# electron_v1_3_0.net
KiCad netlist of a schematic drawn in EAGLE
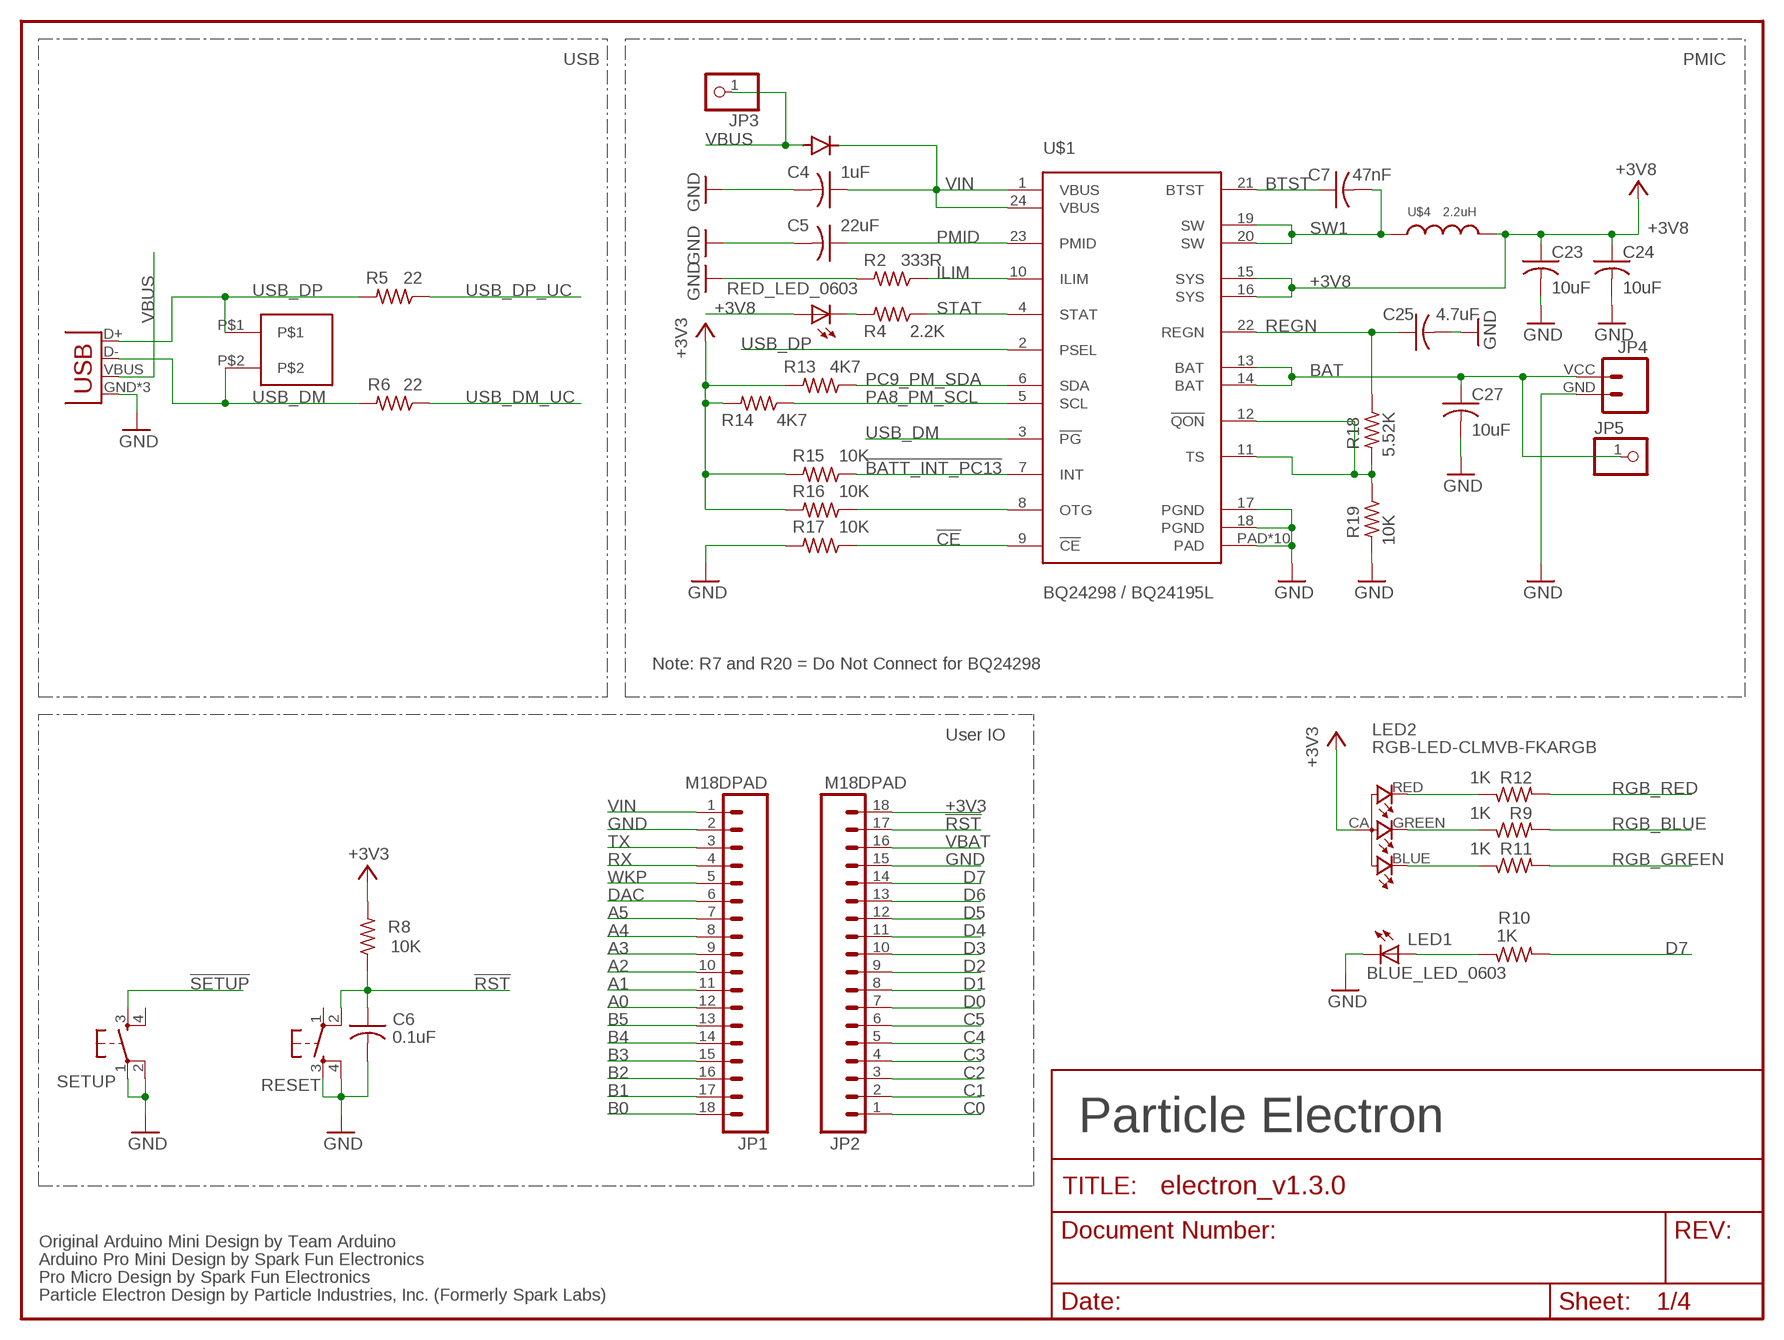
[diagram p0: schematic, sheet 1]
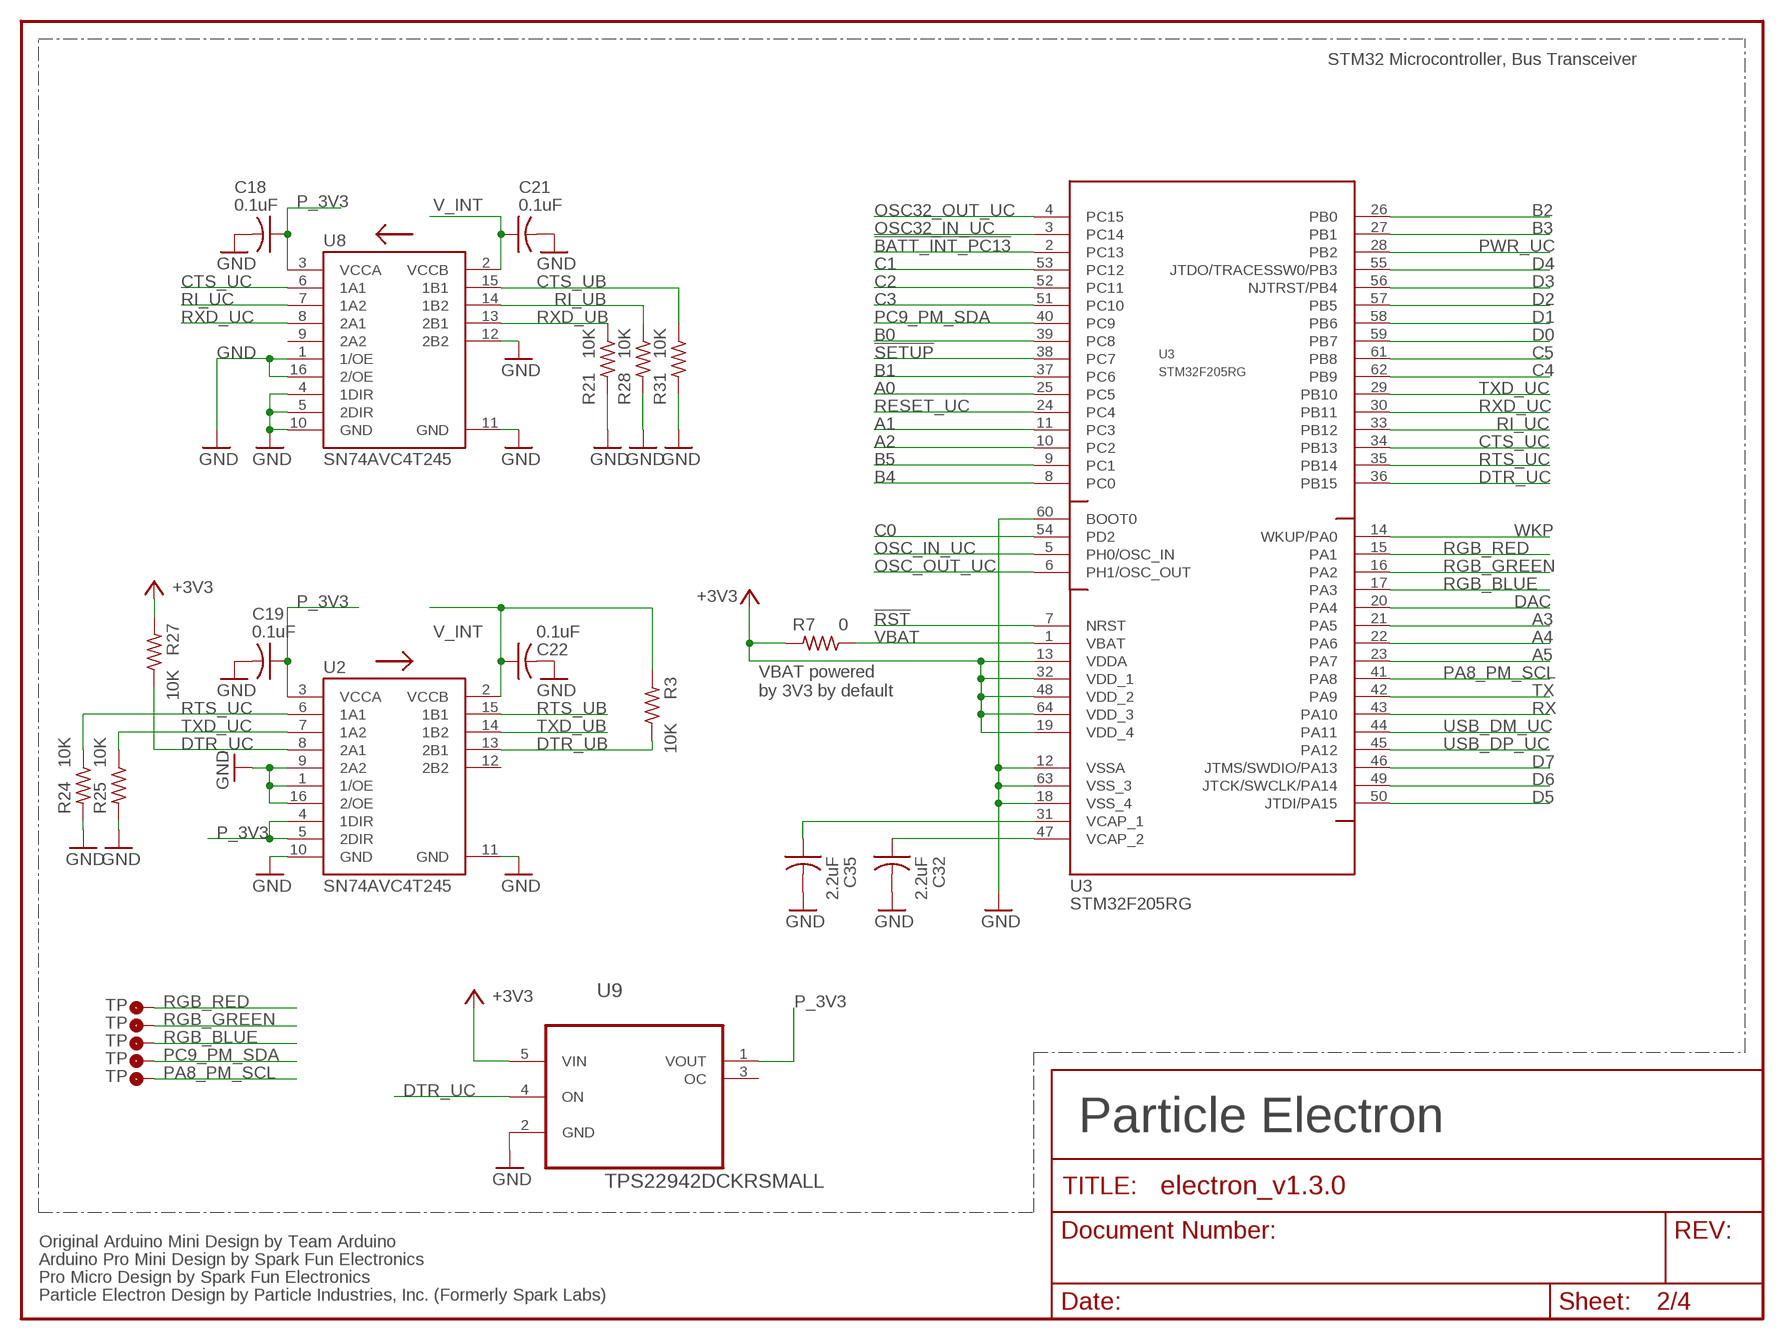
[diagram p1: schematic, sheet 2]
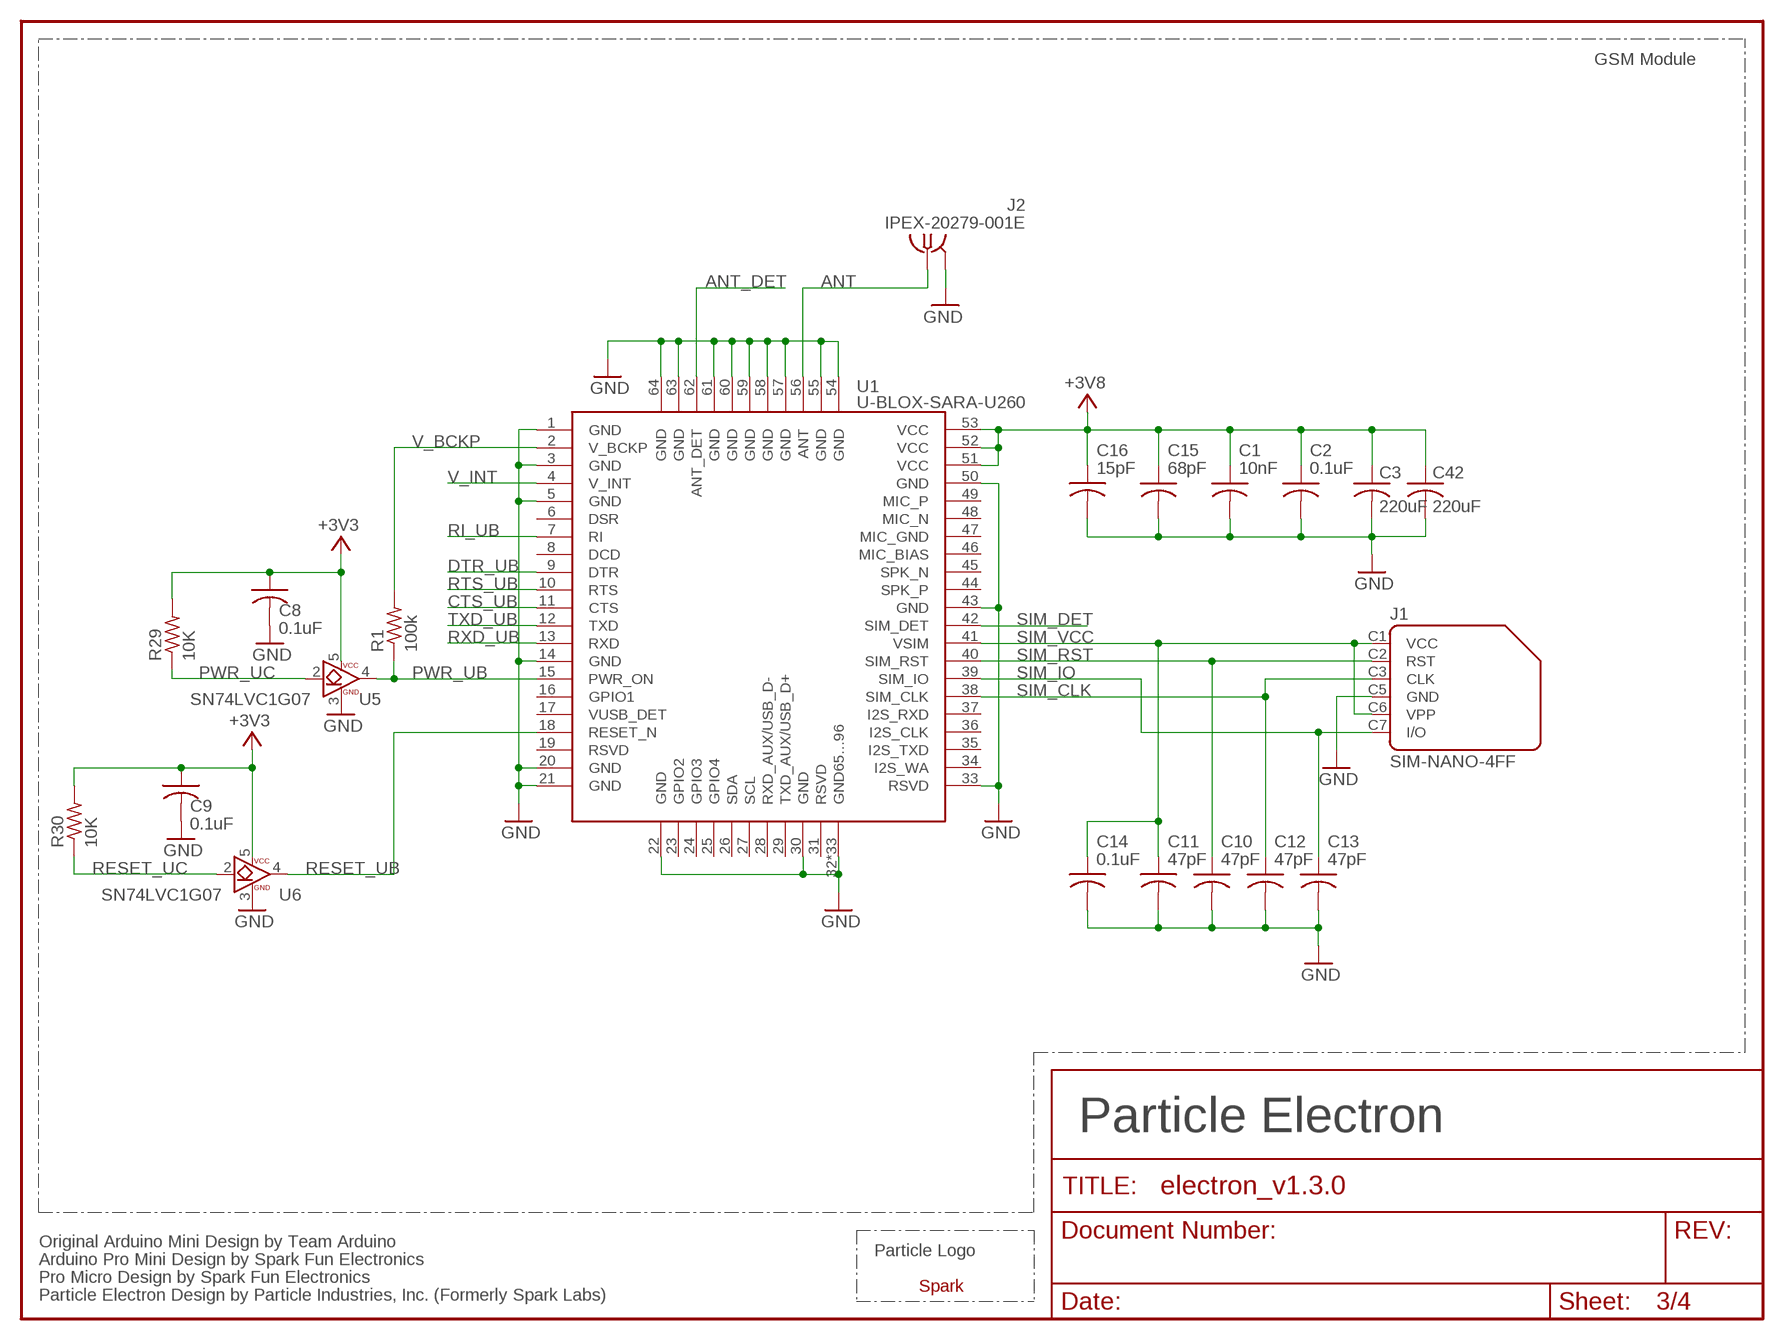
[diagram p2: schematic, sheet 3]
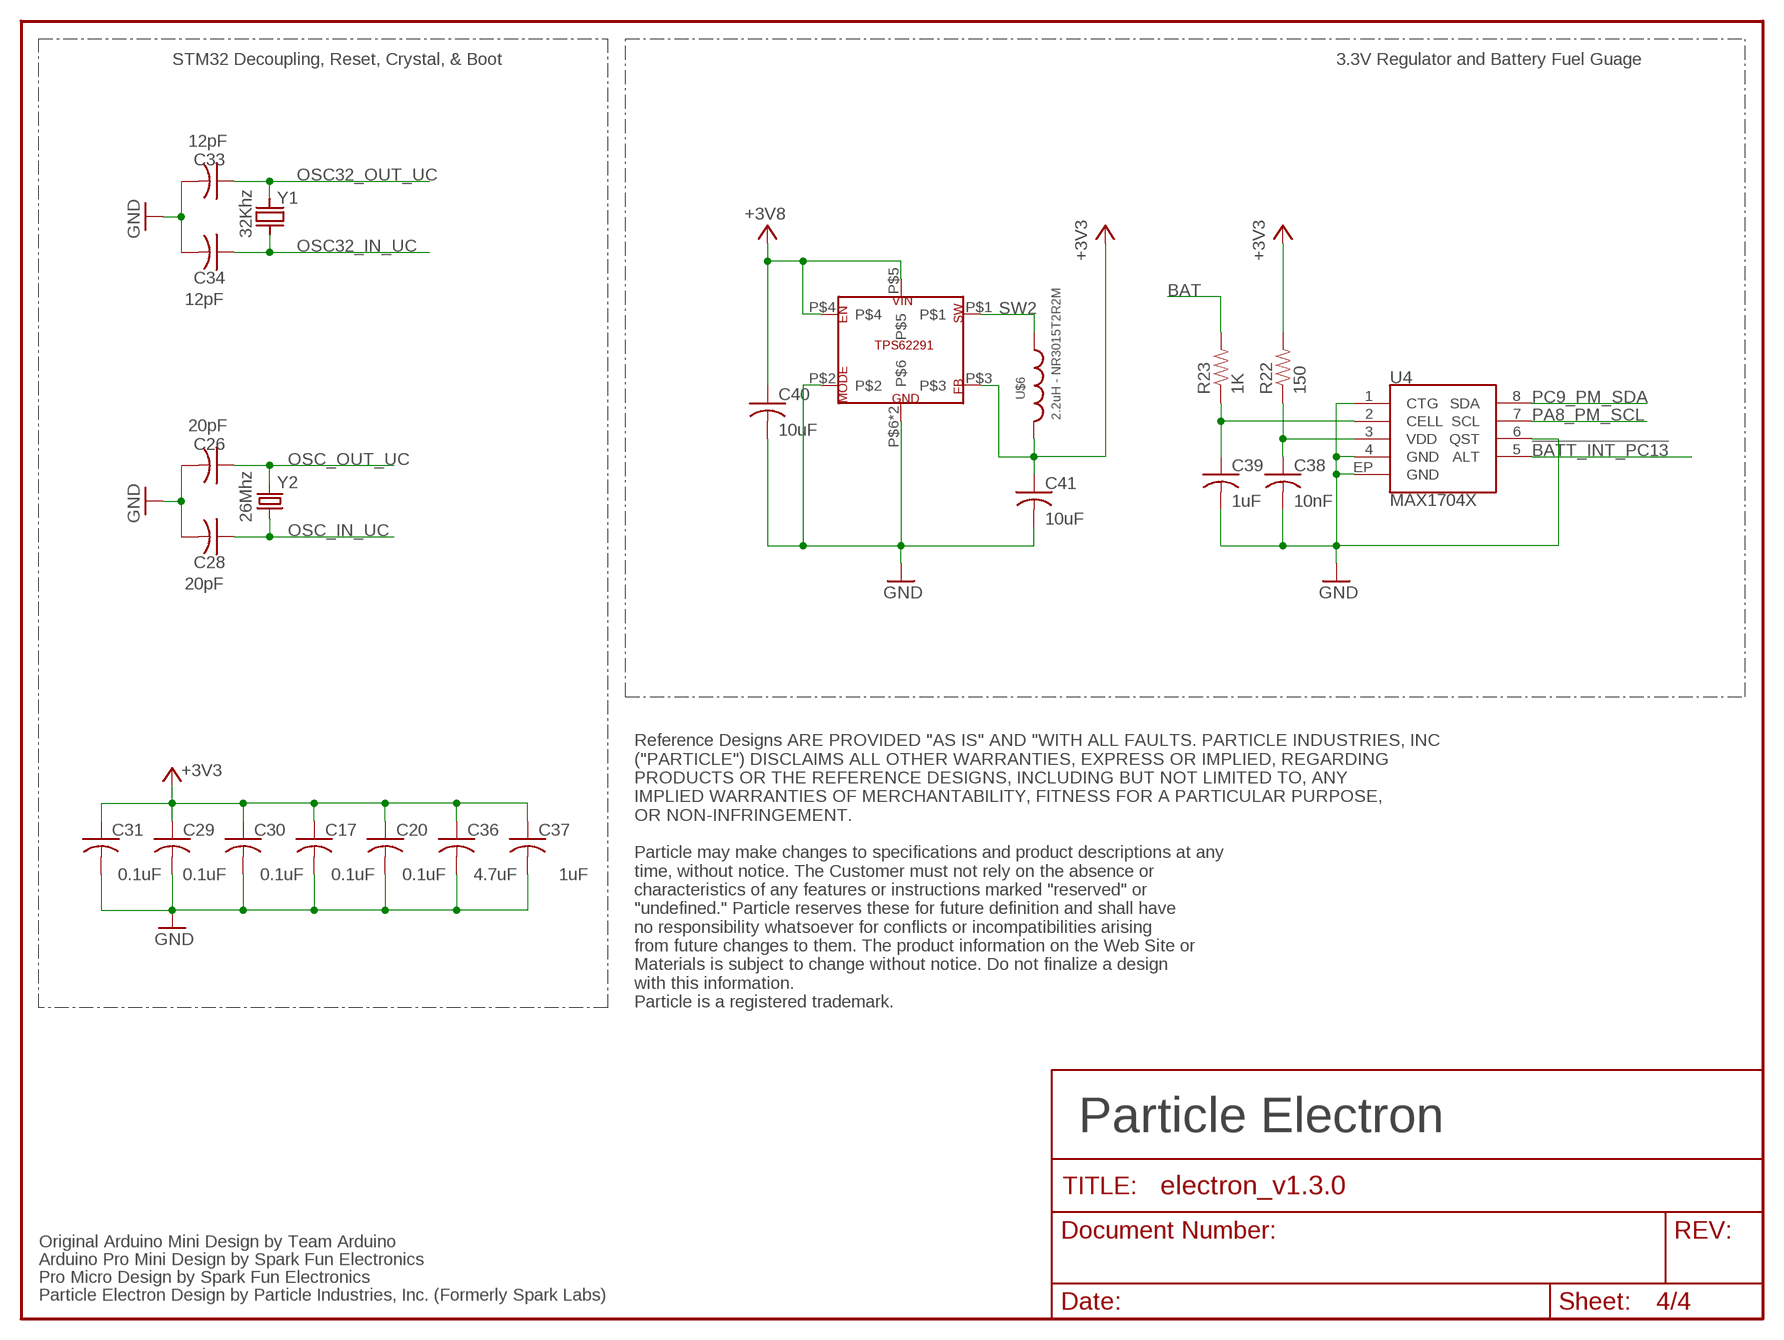
[diagram p3: schematic, sheet 4]

(export (version "E")
  (design (tool "Eeschema 10.0.6"))
  (components
    (comp (ref "C17")
      (value "0.1uF")
      (footprint "eagle-import:C0402_B")
      (libsource (lib "eagle-import") (part "C-US"))
    )
    (comp (ref "C20")
      (value "0.1uF")
      (footprint "eagle-import:C0402_B")
      (libsource (lib "eagle-import") (part "C-US"))
    )
    (comp (ref "C26")
      (value "20pF")
      (footprint "eagle-import:C0402_B")
      (libsource (lib "eagle-import") (part "C-US"))
    )
    (comp (ref "C28")
      (value "20pF")
      (footprint "eagle-import:C0402_B")
      (libsource (lib "eagle-import") (part "C-US"))
    )
    (comp (ref "C29")
      (value "0.1uF")
      (footprint "eagle-import:C0402_B")
      (libsource (lib "eagle-import") (part "C-US"))
    )
    (comp (ref "C30")
      (value "0.1uF")
      (footprint "eagle-import:C0402_B")
      (libsource (lib "eagle-import") (part "C-US"))
    )
    (comp (ref "C31")
      (value "0.1uF")
      (footprint "eagle-import:C0402_B")
      (libsource (lib "eagle-import") (part "C-US"))
    )
    (comp (ref "C33")
      (value "12pF")
      (footprint "eagle-import:C0402_B")
      (libsource (lib "eagle-import") (part "C-US"))
    )
    (comp (ref "C34")
      (value "12pF")
      (footprint "eagle-import:C0402_B")
      (libsource (lib "eagle-import") (part "C-US"))
    )
    (comp (ref "C36")
      (value "4.7uF")
      (footprint "eagle-import:C0402_B")
      (libsource (lib "eagle-import") (part "C-US"))
    )
    (comp (ref "C37")
      (value "1uF")
      (footprint "eagle-import:C0402_B")
      (libsource (lib "eagle-import") (part "C-US"))
    )
    (comp (ref "C38")
      (value "10nF")
      (footprint "eagle-import:C0402_B")
      (libsource (lib "eagle-import") (part "C-US"))
    )
    (comp (ref "C39")
      (value "1uF")
      (footprint "eagle-import:C0402_B")
      (libsource (lib "eagle-import") (part "C-US"))
    )
    (comp (ref "C40")
      (value "10uF")
      (footprint "eagle-import:C0603_B")
      (libsource (lib "eagle-import") (part "C-US0603"))
    )
    (comp (ref "C41")
      (value "10uF")
      (footprint "eagle-import:C0603_B")
      (libsource (lib "eagle-import") (part "C-US0603"))
    )
    (comp (ref "R22")
      (value "150")
      (footprint "eagle-import:0603-RES")
      (libsource (lib "eagle-import") (part "RESISTOR0603-RES"))
    )
    (comp (ref "R23")
      (value "1K")
      (footprint "eagle-import:0603-RES")
      (libsource (lib "eagle-import") (part "RESISTOR0603-RES"))
    )
    (comp (ref "U$5")
      (value "TPS62291DRV")
      (footprint "eagle-import:S-PWSON-N6")
      (libsource (lib "eagle-import") (part "TPS62291DRV"))
    )
    (comp (ref "U$6")
      (value "2.2uH - NR3015T2R2M")
      (footprint "eagle-import:INDUCTOR-NR3015")
      (libsource (lib "eagle-import") (part "INDUCTORB"))
    )
    (comp (ref "U4")
      (value "MAX1704X")
      (footprint "eagle-import:TDFN-8")
      (libsource (lib "eagle-import") (part "MAX1704X"))
    )
    (comp (ref "Y1")
      (value "32Khz")
      (footprint "eagle-import:FC135")
      (libsource (lib "eagle-import") (part "Q_FC135"))
    )
    (comp (ref "Y2")
      (value "26Mhz")
      (footprint "eagle-import:CRYSTAL-SMD-5X3")
      (libsource (lib "eagle-import") (part "CRYSTAL5X3"))
    )
    (comp (ref "C18")
      (value "0.1uF")
      (footprint "eagle-import:C0402_B")
      (libsource (lib "eagle-import") (part "C-US"))
    )
    (comp (ref "C19")
      (value "0.1uF")
      (footprint "eagle-import:C0402_B")
      (libsource (lib "eagle-import") (part "C-US"))
    )
    (comp (ref "C21")
      (value "0.1uF")
      (footprint "eagle-import:C0402_B")
      (libsource (lib "eagle-import") (part "C-US"))
    )
    (comp (ref "C22")
      (value "0.1uF")
      (footprint "eagle-import:C0402_B")
      (libsource (lib "eagle-import") (part "C-US"))
    )
    (comp (ref "C32")
      (value "2.2uF")
      (footprint "eagle-import:C0402_B")
      (libsource (lib "eagle-import") (part "C-US"))
    )
    (comp (ref "C35")
      (value "2.2uF")
      (footprint "eagle-import:C0402_B")
      (libsource (lib "eagle-import") (part "C-US"))
    )
    (comp (ref "R3")
      (value "10K")
      (footprint "eagle-import:R0402_B")
      (libsource (lib "eagle-import") (part "R-US_"))
    )
    (comp (ref "R7")
      (value "0")
      (footprint "eagle-import:R0402_B")
      (libsource (lib "eagle-import") (part "R-US_"))
    )
    (comp (ref "R21")
      (value "10K")
      (footprint "eagle-import:R0402_B")
      (libsource (lib "eagle-import") (part "R-US_"))
    )
    (comp (ref "R24")
      (value "10K")
      (footprint "eagle-import:R0402_B")
      (libsource (lib "eagle-import") (part "R-US_"))
    )
    (comp (ref "R25")
      (value "10K")
      (footprint "eagle-import:R0402_B")
      (libsource (lib "eagle-import") (part "R-US_"))
    )
    (comp (ref "R27")
      (value "10K")
      (footprint "eagle-import:R0402_B")
      (libsource (lib "eagle-import") (part "R-US_"))
    )
    (comp (ref "R28")
      (value "10K")
      (footprint "eagle-import:R0402_B")
      (libsource (lib "eagle-import") (part "R-US_"))
    )
    (comp (ref "R31")
      (value "10K")
      (footprint "eagle-import:R0402_B")
      (libsource (lib "eagle-import") (part "R-US_"))
    )
    (comp (ref "U$8")
      (value "TP0")
      (footprint "eagle-import:TP30_BOT")
      (libsource (lib "eagle-import") (part "TP0"))
    )
    (comp (ref "U$9")
      (value "TP0")
      (footprint "eagle-import:TP30_BOT")
      (libsource (lib "eagle-import") (part "TP0"))
    )
    (comp (ref "U$11")
      (value "TP0")
      (footprint "eagle-import:TP30_BOT")
      (libsource (lib "eagle-import") (part "TP0"))
    )
    (comp (ref "U$12")
      (value "TP0")
      (footprint "eagle-import:TP30_BOT")
      (libsource (lib "eagle-import") (part "TP0"))
    )
    (comp (ref "U$13")
      (value "TP0")
      (footprint "eagle-import:TP30_BOT")
      (libsource (lib "eagle-import") (part "TP0"))
    )
    (comp (ref "U2")
      (value "SN74AVC4T245")
      (footprint "eagle-import:UFQFN-16")
      (libsource (lib "eagle-import") (part "SN74AVC4T245"))
    )
    (comp (ref "U3")
      (value "STM32F205RG")
      (footprint "eagle-import:LQFP64")
      (libsource (lib "eagle-import") (part "STM32F20XR"))
    )
    (comp (ref "U8")
      (value "SN74AVC4T245")
      (footprint "eagle-import:UFQFN-16")
      (libsource (lib "eagle-import") (part "SN74AVC4T245"))
    )
    (comp (ref "U9")
      (value "TPS22942DCKRSMALL")
      (footprint "eagle-import:SC70-5")
      (libsource (lib "eagle-import") (part "TPS22942DCKRSMALL"))
    )
    (comp (ref "BLUE_LED_0603")
      (value "LEDNOSILK")
      (footprint "eagle-import:LED-0603-NS")
      (libsource (lib "eagle-import") (part "LEDNOSILK"))
    )
    (comp (ref "C4")
      (value "1uF")
      (footprint "eagle-import:C0603_B")
      (libsource (lib "eagle-import") (part "C-US0603"))
    )
    (comp (ref "C5")
      (value "22uF")
      (footprint "eagle-import:C0603_B")
      (libsource (lib "eagle-import") (part "C-US0603"))
    )
    (comp (ref "C6")
      (value "0.1uF")
      (footprint "eagle-import:C0402_B")
      (libsource (lib "eagle-import") (part "C-US"))
    )
    (comp (ref "C7")
      (value "47nF")
      (footprint "eagle-import:C0402_B")
      (libsource (lib "eagle-import") (part "C-US"))
    )
    (comp (ref "C23")
      (value "10uF")
      (footprint "eagle-import:C0603_B")
      (libsource (lib "eagle-import") (part "C-US0603"))
    )
    (comp (ref "C24")
      (value "10uF")
      (footprint "eagle-import:C0603_B")
      (libsource (lib "eagle-import") (part "C-US0603"))
    )
    (comp (ref "C25")
      (value "4.7uF")
      (footprint "eagle-import:C0603_B")
      (libsource (lib "eagle-import") (part "C-US0603"))
    )
    (comp (ref "C27")
      (value "10uF")
      (footprint "eagle-import:C0603_B")
      (libsource (lib "eagle-import") (part "C-US0603"))
    )
    (comp (ref "JP1")
      (value "M18DPAD")
      (footprint "eagle-import:1X18-D-PADS")
      (libsource (lib "eagle-import") (part "M18DPAD"))
    )
    (comp (ref "JP2")
      (value "M18DPAD")
      (footprint "eagle-import:1X18-D-PADS")
      (libsource (lib "eagle-import") (part "M18DPAD"))
    )
    (comp (ref "JP3")
      (value "PINHD-1X1NOSILK")
      (footprint "eagle-import:1X01_NO_SILK")
      (libsource (lib "eagle-import") (part "PINHD-1X1NOSILK"))
    )
    (comp (ref "JP4")
      (value "M024UCON-15767")
      (footprint "eagle-import:JST-2-SMD-VERT")
      (libsource (lib "eagle-import") (part "M024UCON-15767"))
    )
    (comp (ref "JP5")
      (value "PINHD-1X1NOSILK")
      (footprint "eagle-import:1X01_NO_SILK")
      (libsource (lib "eagle-import") (part "PINHD-1X1NOSILK"))
    )
    (comp (ref "LED2")
      (value "RGB-LED-CLMVB-FKARGB")
      (footprint "eagle-import:PLCC4-2MM-RGB")
      (libsource (lib "eagle-import") (part "RGB-LED-CLMVB-FKARGB"))
    )
    (comp (ref "R2")
      (value "333R")
      (footprint "eagle-import:R0402_B")
      (libsource (lib "eagle-import") (part "R-US_"))
    )
    (comp (ref "R4")
      (value "2.2K")
      (footprint "eagle-import:R0402_B")
      (libsource (lib "eagle-import") (part "R-US_"))
    )
    (comp (ref "R5")
      (value "22")
      (footprint "eagle-import:R0402_B")
      (libsource (lib "eagle-import") (part "R-US_"))
    )
    (comp (ref "R6")
      (value "22")
      (footprint "eagle-import:R0402_B")
      (libsource (lib "eagle-import") (part "R-US_"))
    )
    (comp (ref "R8")
      (value "10K")
      (footprint "eagle-import:R0402_B")
      (libsource (lib "eagle-import") (part "R-US_"))
    )
    (comp (ref "R9")
      (value "1K")
      (footprint "eagle-import:R0402_B")
      (libsource (lib "eagle-import") (part "R-US_"))
    )
    (comp (ref "R10")
      (value "1K")
      (footprint "eagle-import:R0402_B")
      (libsource (lib "eagle-import") (part "R-US_"))
    )
    (comp (ref "R11")
      (value "1K")
      (footprint "eagle-import:R0402_B")
      (libsource (lib "eagle-import") (part "R-US_"))
    )
    (comp (ref "R12")
      (value "1K")
      (footprint "eagle-import:R0402_B")
      (libsource (lib "eagle-import") (part "R-US_"))
    )
    (comp (ref "R13")
      (value "4K7")
      (footprint "eagle-import:R0402_B")
      (libsource (lib "eagle-import") (part "R-US_"))
    )
    (comp (ref "R14")
      (value "4K7")
      (footprint "eagle-import:R0402_B")
      (libsource (lib "eagle-import") (part "R-US_"))
    )
    (comp (ref "R15")
      (value "10K")
      (footprint "eagle-import:R0402_B")
      (libsource (lib "eagle-import") (part "R-US_"))
    )
    (comp (ref "R16")
      (value "10K")
      (footprint "eagle-import:R0402_B")
      (libsource (lib "eagle-import") (part "R-US_"))
    )
    (comp (ref "R17")
      (value "10K")
      (footprint "eagle-import:R0402_B")
      (libsource (lib "eagle-import") (part "R-US_"))
    )
    (comp (ref "R18")
      (value "5.52K")
      (footprint "eagle-import:R0402_B")
      (libsource (lib "eagle-import") (part "R-US_"))
    )
    (comp (ref "R19")
      (value "10K")
      (footprint "eagle-import:R0402_B")
      (libsource (lib "eagle-import") (part "R-US_"))
    )
    (comp (ref "RED_LED_0603")
      (value "LED0603")
      (footprint "eagle-import:LED-0603")
      (libsource (lib "eagle-import") (part "LED0603"))
    )
    (comp (ref "RESET")
      (value "KMR211GLFS")
      (footprint "eagle-import:TACTILE_SWITCH_SMD")
      (libsource (lib "eagle-import") (part "TAC_SWITCHSMD"))
    )
    (comp (ref "SETUP")
      (value "KMR211GLFS")
      (footprint "eagle-import:TACTILE_SWITCH_SMD")
      (libsource (lib "eagle-import") (part "TAC_SWITCHSMD"))
    )
    (comp (ref "U$1")
      (value "BQ24298 / BQ24195L")
      (footprint "eagle-import:QFN24")
      (libsource (lib "eagle-import") (part "BQ24298RTWR"))
    )
    (comp (ref "U$3")
      (value "DIODE_NT")
      (footprint "eagle-import:DIODE-DO-220AA_NT(SMP)")
      (libsource (lib "eagle-import") (part "DIODE_NT"))
    )
    (comp (ref "U$4")
      (value "2.2uH")
      (footprint "eagle-import:INDUCTOR-4040")
      (libsource (lib "eagle-import") (part "INDUCTORI"))
    )
    (comp (ref "U$7")
      (value "M02_0.05_HEADER")
      (footprint "eagle-import:M02_0.05_HEADER")
      (libsource (lib "eagle-import") (part "M02_0.05_HEADER"))
    )
    (comp (ref "X1")
      (value "USB-MICROB")
      (footprint "eagle-import:USB-MICROB-SLOT-HOLE")
      (libsource (lib "eagle-import") (part "USBUSB-MICROB-SLOT-HOLE"))
    )
    (comp (ref "C1")
      (value "10nF")
      (footprint "eagle-import:C0402_B")
      (libsource (lib "eagle-import") (part "C-US"))
    )
    (comp (ref "C2")
      (value "0.1uF")
      (footprint "eagle-import:C0402_B")
      (libsource (lib "eagle-import") (part "C-US"))
    )
    (comp (ref "C3")
      (value "220uF")
      (footprint "eagle-import:C1210")
      (libsource (lib "eagle-import") (part "C-USC1210"))
    )
    (comp (ref "C8")
      (value "0.1uF")
      (footprint "eagle-import:C0402_B")
      (libsource (lib "eagle-import") (part "C-US"))
    )
    (comp (ref "C9")
      (value "0.1uF")
      (footprint "eagle-import:C0402_B")
      (libsource (lib "eagle-import") (part "C-US"))
    )
    (comp (ref "C10")
      (value "47pF")
      (footprint "eagle-import:C0402_B")
      (libsource (lib "eagle-import") (part "C-US"))
    )
    (comp (ref "C11")
      (value "47pF")
      (footprint "eagle-import:C0402_B")
      (libsource (lib "eagle-import") (part "C-US"))
    )
    (comp (ref "C12")
      (value "47pF")
      (footprint "eagle-import:C0402_B")
      (libsource (lib "eagle-import") (part "C-US"))
    )
    (comp (ref "C13")
      (value "47pF")
      (footprint "eagle-import:C0402_B")
      (libsource (lib "eagle-import") (part "C-US"))
    )
    (comp (ref "C14")
      (value "0.1uF")
      (footprint "eagle-import:C0402_B")
      (libsource (lib "eagle-import") (part "C-US"))
    )
    (comp (ref "C15")
      (value "68pF")
      (footprint "eagle-import:C0402_B")
      (libsource (lib "eagle-import") (part "C-US"))
    )
    (comp (ref "C16")
      (value "15pF")
      (footprint "eagle-import:C0402_B")
      (libsource (lib "eagle-import") (part "C-US"))
    )
    (comp (ref "C42")
      (value "220uF")
      (footprint "eagle-import:C1210")
      (libsource (lib "eagle-import") (part "C-USC1210"))
    )
    (comp (ref "J1")
      (value "SIM-NANO-4FF")
      (footprint "eagle-import:GCT-SIM8100")
      (libsource (lib "eagle-import") (part "SIM-NANO-4FF"))
    )
    (comp (ref "J2")
      (value "IPEX-20279-001E")
      (footprint "eagle-import:IPEX-20279-001E")
      (libsource (lib "eagle-import") (part "IPEX-20279-001E"))
    )
    (comp (ref "R1")
      (value "100k")
      (footprint "eagle-import:R0402_B")
      (libsource (lib "eagle-import") (part "R-US_"))
    )
    (comp (ref "R29")
      (value "10K")
      (footprint "eagle-import:R0402_B")
      (libsource (lib "eagle-import") (part "R-US_"))
    )
    (comp (ref "R30")
      (value "10K")
      (footprint "eagle-import:R0402_B")
      (libsource (lib "eagle-import") (part "R-US_"))
    )
    (comp (ref "U$2")
      (value "SPARK_LOGO2")
      (footprint "eagle-import:SPARK_LOGO2")
      (libsource (lib "eagle-import") (part "SPARK_LOGO2"))
    )
    (comp (ref "U1")
      (value "U-BLOX-SARA-U260")
      (footprint "eagle-import:U-BLOX-SARA-U2")
      (libsource (lib "eagle-import") (part "U-BLOX-SARA-U260"))
    )
    (comp (ref "U5")
      (value "SN74LVC1G07")
      (footprint "eagle-import:SC-70-5")
      (libsource (lib "eagle-import") (part "SN74LVC1G07"))
    )
    (comp (ref "U6")
      (value "SN74LVC1G07")
      (footprint "eagle-import:SC-70-5")
      (libsource (lib "eagle-import") (part "SN74LVC1G07"))
    )
  )
  (nets
    (net (code "1") (name "+3V3") (class "Default")
      (node (ref "C17") (pin "1") (pinfunction "1_1") (pintype "passive"))
      (node (ref "C20") (pin "1") (pinfunction "1_1") (pintype "passive"))
      (node (ref "C29") (pin "1") (pinfunction "1_1") (pintype "passive"))
      (node (ref "C30") (pin "1") (pinfunction "1_1") (pintype "passive"))
      (node (ref "C31") (pin "1") (pinfunction "1_1") (pintype "passive"))
      (node (ref "C36") (pin "1") (pinfunction "1_1") (pintype "passive"))
      (node (ref "C37") (pin "1") (pinfunction "1_1") (pintype "passive"))
      (node (ref "C41") (pin "1") (pinfunction "1_1") (pintype "passive"))
      (node (ref "C8") (pin "1") (pinfunction "1_1") (pintype "passive"))
      (node (ref "C9") (pin "1") (pinfunction "1_1") (pintype "passive"))
      (node (ref "JP2") (pin "18") (pinfunction "18_18") (pintype "passive"))
      (node (ref "LED2") (pin "CA") (pinfunction "1_CA") (pintype "passive"))
      (node (ref "R13") (pin "2") (pinfunction "2_2") (pintype "passive"))
      (node (ref "R14") (pin "2") (pinfunction "2_2") (pintype "passive"))
      (node (ref "R15") (pin "2") (pinfunction "2_2") (pintype "passive"))
      (node (ref "R16") (pin "2") (pinfunction "2_2") (pintype "passive"))
      (node (ref "R22") (pin "2") (pinfunction "2_2") (pintype "passive"))
      (node (ref "R27") (pin "2") (pinfunction "2_2") (pintype "passive"))
      (node (ref "R29") (pin "2") (pinfunction "2_2") (pintype "passive"))
      (node (ref "R30") (pin "2") (pinfunction "2_2") (pintype "passive"))
      (node (ref "R7") (pin "2") (pinfunction "2_2") (pintype "passive"))
      (node (ref "R8") (pin "2") (pinfunction "2_2") (pintype "passive"))
      (node (ref "U$5") (pin "P$3") (pinfunction "P$3_P$3") (pintype "bidirectional"))
      (node (ref "U$6") (pin "2") (pinfunction "2_2") (pintype "passive"))
      (node (ref "U3") (pin "13") (pinfunction "VDDA_13") (pintype "power_in"))
      (node (ref "U3") (pin "19") (pinfunction "VDD_4_19") (pintype "power_in"))
      (node (ref "U3") (pin "32") (pinfunction "VDD_1_32") (pintype "power_in"))
      (node (ref "U3") (pin "48") (pinfunction "VDD_2_48") (pintype "power_in"))
      (node (ref "U3") (pin "64") (pinfunction "VDD_3_64") (pintype "power_in"))
      (node (ref "U5") (pin "5") (pinfunction "VCC_5") (pintype "bidirectional"))
      (node (ref "U6") (pin "5") (pinfunction "VCC_5") (pintype "bidirectional"))
      (node (ref "U9") (pin "5") (pinfunction "VIN_5") (pintype "power_in"))
    )
    (net (code "2") (name "+3V8") (class "Default")
      (node (ref "C1") (pin "1") (pinfunction "1_1") (pintype "passive"))
      (node (ref "C15") (pin "1") (pinfunction "1_1") (pintype "passive"))
      (node (ref "C16") (pin "1") (pinfunction "1_1") (pintype "passive"))
      (node (ref "C2") (pin "1") (pinfunction "1_1") (pintype "passive"))
      (node (ref "C23") (pin "1") (pinfunction "1_1") (pintype "passive"))
      (node (ref "C24") (pin "1") (pinfunction "1_1") (pintype "passive"))
      (node (ref "C3") (pin "1") (pinfunction "1_1") (pintype "passive"))
      (node (ref "C40") (pin "1") (pinfunction "1_1") (pintype "passive"))
      (node (ref "C42") (pin "1") (pinfunction "1_1") (pintype "passive"))
      (node (ref "RED_LED_0603") (pin "A") (pinfunction "A_A") (pintype "passive"))
      (node (ref "U$1") (pin "15") (pinfunction "SYS_15") (pintype "power_in"))
      (node (ref "U$1") (pin "16") (pinfunction "SYS_16") (pintype "power_in"))
      (node (ref "U$4") (pin "P$2") (pinfunction "2_P$2") (pintype "passive"))
      (node (ref "U$5") (pin "P$4") (pinfunction "P$4_P$4") (pintype "bidirectional"))
      (node (ref "U$5") (pin "P$5") (pinfunction "P$5_P$5") (pintype "bidirectional"))
      (node (ref "U1") (pin "51") (pinfunction "VCC_51") (pintype "bidirectional"))
      (node (ref "U1") (pin "52") (pinfunction "VCC_52") (pintype "bidirectional"))
      (node (ref "U1") (pin "53") (pinfunction "VCC_53") (pintype "bidirectional"))
    )
    (net (code "3") (name "A0") (class "Default")
      (node (ref "JP1") (pin "12") (pinfunction "12_12") (pintype "passive"))
      (node (ref "U3") (pin "25") (pinfunction "PC5_25") (pintype "bidirectional"))
    )
    (net (code "4") (name "A1") (class "Default")
      (node (ref "JP1") (pin "11") (pinfunction "11_11") (pintype "passive"))
      (node (ref "U3") (pin "11") (pinfunction "PC3_11") (pintype "bidirectional"))
    )
    (net (code "5") (name "A2") (class "Default")
      (node (ref "JP1") (pin "10") (pinfunction "10_10") (pintype "passive"))
      (node (ref "U3") (pin "10") (pinfunction "PC2_10") (pintype "bidirectional"))
    )
    (net (code "6") (name "A3") (class "Default")
      (node (ref "JP1") (pin "9") (pinfunction "9_9") (pintype "passive"))
      (node (ref "U3") (pin "21") (pinfunction "PA5_21") (pintype "bidirectional"))
    )
    (net (code "7") (name "A4") (class "Default")
      (node (ref "JP1") (pin "8") (pinfunction "8_8") (pintype "passive"))
      (node (ref "U3") (pin "22") (pinfunction "PA6_22") (pintype "bidirectional"))
    )
    (net (code "8") (name "A5") (class "Default")
      (node (ref "JP1") (pin "7") (pinfunction "7_7") (pintype "passive"))
      (node (ref "U3") (pin "23") (pinfunction "PA7_23") (pintype "bidirectional"))
    )
    (net (code "9") (name "ANT") (class "Default")
      (node (ref "J2") (pin "1") (pinfunction "1_1") (pintype "passive"))
      (node (ref "U1") (pin "56") (pinfunction "ANT_56") (pintype "bidirectional"))
    )
    (net (code "10") (name "ANT_DET") (class "Default")
      (node (ref "U1") (pin "62") (pinfunction "ANT_DET_62") (pintype "bidirectional"))
    )
    (net (code "11") (name "B0") (class "Default")
      (node (ref "JP1") (pin "18") (pinfunction "18_18") (pintype "passive"))
      (node (ref "U3") (pin "39") (pinfunction "PC8_39") (pintype "bidirectional"))
    )
    (net (code "12") (name "B1") (class "Default")
      (node (ref "JP1") (pin "17") (pinfunction "17_17") (pintype "passive"))
      (node (ref "U3") (pin "37") (pinfunction "PC6_37") (pintype "bidirectional"))
    )
    (net (code "13") (name "B2") (class "Default")
      (node (ref "JP1") (pin "16") (pinfunction "16_16") (pintype "passive"))
      (node (ref "U3") (pin "26") (pinfunction "PB0_26") (pintype "bidirectional"))
    )
    (net (code "14") (name "B3") (class "Default")
      (node (ref "JP1") (pin "15") (pinfunction "15_15") (pintype "passive"))
      (node (ref "U3") (pin "27") (pinfunction "PB1_27") (pintype "bidirectional"))
    )
    (net (code "15") (name "B4") (class "Default")
      (node (ref "JP1") (pin "14") (pinfunction "14_14") (pintype "passive"))
      (node (ref "U3") (pin "8") (pinfunction "PC0_8") (pintype "bidirectional"))
    )
    (net (code "16") (name "B5") (class "Default")
      (node (ref "JP1") (pin "13") (pinfunction "13_13") (pintype "passive"))
      (node (ref "U3") (pin "9") (pinfunction "PC1_9") (pintype "bidirectional"))
    )
    (net (code "17") (name "BAT") (class "Default")
      (node (ref "C27") (pin "1") (pinfunction "1_1") (pintype "passive"))
      (node (ref "JP4") (pin "VCC") (pinfunction "2_VCC") (pintype "passive"))
      (node (ref "JP5") (pin "1") (pinfunction "1_1") (pintype "passive"))
      (node (ref "R23") (pin "2") (pinfunction "2_2") (pintype "passive"))
      (node (ref "U$1") (pin "13") (pinfunction "BAT_13") (pintype "passive"))
      (node (ref "U$1") (pin "14") (pinfunction "BAT_14") (pintype "power_in"))
    )
    (net (code "18") (name "BTST") (class "Default")
      (node (ref "C7") (pin "1") (pinfunction "1_1") (pintype "passive"))
      (node (ref "U$1") (pin "21") (pinfunction "BTST_21") (pintype "bidirectional"))
    )
    (net (code "19") (name "C0") (class "Default")
      (node (ref "JP2") (pin "1") (pinfunction "1_1") (pintype "passive"))
      (node (ref "U3") (pin "54") (pinfunction "PD2_54") (pintype "bidirectional"))
    )
    (net (code "20") (name "C1") (class "Default")
      (node (ref "JP2") (pin "2") (pinfunction "2_2") (pintype "passive"))
      (node (ref "U3") (pin "53") (pinfunction "PC12_53") (pintype "bidirectional"))
    )
    (net (code "21") (name "C2") (class "Default")
      (node (ref "JP2") (pin "3") (pinfunction "3_3") (pintype "passive"))
      (node (ref "U3") (pin "52") (pinfunction "PC11_52") (pintype "bidirectional"))
    )
    (net (code "22") (name "C3") (class "Default")
      (node (ref "JP2") (pin "4") (pinfunction "4_4") (pintype "passive"))
      (node (ref "U3") (pin "51") (pinfunction "PC10_51") (pintype "bidirectional"))
    )
    (net (code "23") (name "C4") (class "Default")
      (node (ref "JP2") (pin "5") (pinfunction "5_5") (pintype "passive"))
      (node (ref "U3") (pin "62") (pinfunction "PB9_62") (pintype "bidirectional"))
    )
    (net (code "24") (name "C5") (class "Default")
      (node (ref "JP2") (pin "6") (pinfunction "6_6") (pintype "passive"))
      (node (ref "U3") (pin "61") (pinfunction "PB8_61") (pintype "bidirectional"))
    )
    (net (code "25") (name "CTS_UB") (class "Default")
      (node (ref "R31") (pin "1") (pinfunction "1_1") (pintype "passive"))
      (node (ref "U1") (pin "11") (pinfunction "CTS_11") (pintype "bidirectional"))
      (node (ref "U8") (pin "15") (pinfunction "1B1_15") (pintype "bidirectional"))
    )
    (net (code "26") (name "CTS_UC") (class "Default")
      (node (ref "U3") (pin "34") (pinfunction "PB13_34") (pintype "bidirectional"))
      (node (ref "U8") (pin "6") (pinfunction "1A1_6") (pintype "bidirectional"))
    )
    (net (code "27") (name "D0") (class "Default")
      (node (ref "JP2") (pin "7") (pinfunction "7_7") (pintype "passive"))
      (node (ref "U3") (pin "59") (pinfunction "PB7_59") (pintype "bidirectional"))
    )
    (net (code "28") (name "D1") (class "Default")
      (node (ref "JP2") (pin "8") (pinfunction "8_8") (pintype "passive"))
      (node (ref "U3") (pin "58") (pinfunction "PB6_58") (pintype "bidirectional"))
    )
    (net (code "29") (name "D2") (class "Default")
      (node (ref "JP2") (pin "9") (pinfunction "9_9") (pintype "passive"))
      (node (ref "U3") (pin "57") (pinfunction "PB5_57") (pintype "bidirectional"))
    )
    (net (code "30") (name "D3") (class "Default")
      (node (ref "JP2") (pin "10") (pinfunction "10_10") (pintype "passive"))
      (node (ref "U3") (pin "56") (pinfunction "NJTRST/PB4_56") (pintype "bidirectional"))
    )
    (net (code "31") (name "D4") (class "Default")
      (node (ref "JP2") (pin "11") (pinfunction "11_11") (pintype "passive"))
      (node (ref "U3") (pin "55") (pinfunction "JTDO/TRACESSW0/PB3_55") (pintype "bidirectional"))
    )
    (net (code "32") (name "D5") (class "Default")
      (node (ref "JP2") (pin "12") (pinfunction "12_12") (pintype "passive"))
      (node (ref "U3") (pin "50") (pinfunction "JTDI/PA15_50") (pintype "bidirectional"))
    )
    (net (code "33") (name "D6") (class "Default")
      (node (ref "JP2") (pin "13") (pinfunction "13_13") (pintype "passive"))
      (node (ref "U3") (pin "49") (pinfunction "JTCK/SWCLK/PA14_49") (pintype "bidirectional"))
    )
    (net (code "34") (name "D7") (class "Default")
      (node (ref "JP2") (pin "14") (pinfunction "14_14") (pintype "passive"))
      (node (ref "R10") (pin "2") (pinfunction "2_2") (pintype "passive"))
      (node (ref "U3") (pin "46") (pinfunction "JTMS/SWDIO/PA13_46") (pintype "bidirectional"))
    )
    (net (code "35") (name "DAC") (class "Default")
      (node (ref "JP1") (pin "6") (pinfunction "6_6") (pintype "passive"))
      (node (ref "U3") (pin "20") (pinfunction "PA4_20") (pintype "bidirectional"))
    )
    (net (code "36") (name "DTR_UB") (class "Default")
      (node (ref "R3") (pin "1") (pinfunction "1_1") (pintype "passive"))
      (node (ref "U1") (pin "9") (pinfunction "DTR_9") (pintype "bidirectional"))
      (node (ref "U2") (pin "13") (pinfunction "2B1_13") (pintype "bidirectional"))
    )
    (net (code "37") (name "DTR_UC") (class "Default")
      (node (ref "R27") (pin "1") (pinfunction "1_1") (pintype "passive"))
      (node (ref "U2") (pin "8") (pinfunction "2A1_8") (pintype "bidirectional"))
      (node (ref "U3") (pin "36") (pinfunction "PB15_36") (pintype "bidirectional"))
      (node (ref "U9") (pin "4") (pinfunction "ON_4") (pintype "input"))
    )
    (net (code "38") (name "GND") (class "Default")
      (node (ref "BLUE_LED_0603") (pin "C") (pinfunction "C_C") (pintype "passive"))
      (node (ref "C1") (pin "2") (pinfunction "2_2") (pintype "passive"))
      (node (ref "C10") (pin "2") (pinfunction "2_2") (pintype "passive"))
      (node (ref "C11") (pin "2") (pinfunction "2_2") (pintype "passive"))
      (node (ref "C12") (pin "2") (pinfunction "2_2") (pintype "passive"))
      (node (ref "C13") (pin "2") (pinfunction "2_2") (pintype "passive"))
      (node (ref "C14") (pin "2") (pinfunction "2_2") (pintype "passive"))
      (node (ref "C15") (pin "2") (pinfunction "2_2") (pintype "passive"))
      (node (ref "C16") (pin "2") (pinfunction "2_2") (pintype "passive"))
      (node (ref "C17") (pin "2") (pinfunction "2_2") (pintype "passive"))
      (node (ref "C18") (pin "2") (pinfunction "2_2") (pintype "passive"))
      (node (ref "C19") (pin "2") (pinfunction "2_2") (pintype "passive"))
      (node (ref "C2") (pin "2") (pinfunction "2_2") (pintype "passive"))
      (node (ref "C20") (pin "2") (pinfunction "2_2") (pintype "passive"))
      (node (ref "C21") (pin "2") (pinfunction "2_2") (pintype "passive"))
      (node (ref "C22") (pin "2") (pinfunction "2_2") (pintype "passive"))
      (node (ref "C23") (pin "2") (pinfunction "2_2") (pintype "passive"))
      (node (ref "C24") (pin "2") (pinfunction "2_2") (pintype "passive"))
      (node (ref "C25") (pin "2") (pinfunction "2_2") (pintype "passive"))
      (node (ref "C26") (pin "2") (pinfunction "2_2") (pintype "passive"))
      (node (ref "C27") (pin "2") (pinfunction "2_2") (pintype "passive"))
      (node (ref "C28") (pin "2") (pinfunction "2_2") (pintype "passive"))
      (node (ref "C29") (pin "2") (pinfunction "2_2") (pintype "passive"))
      (node (ref "C3") (pin "2") (pinfunction "2_2") (pintype "passive"))
      (node (ref "C30") (pin "2") (pinfunction "2_2") (pintype "passive"))
      (node (ref "C31") (pin "2") (pinfunction "2_2") (pintype "passive"))
      (node (ref "C32") (pin "2") (pinfunction "2_2") (pintype "passive"))
      (node (ref "C33") (pin "2") (pinfunction "2_2") (pintype "passive"))
      (node (ref "C34") (pin "2") (pinfunction "2_2") (pintype "passive"))
      (node (ref "C35") (pin "2") (pinfunction "2_2") (pintype "passive"))
      (node (ref "C36") (pin "2") (pinfunction "2_2") (pintype "passive"))
      (node (ref "C37") (pin "2") (pinfunction "2_2") (pintype "passive"))
      (node (ref "C38") (pin "2") (pinfunction "2_2") (pintype "passive"))
      (node (ref "C39") (pin "2") (pinfunction "2_2") (pintype "passive"))
      (node (ref "C4") (pin "2") (pinfunction "2_2") (pintype "passive"))
      (node (ref "C40") (pin "2") (pinfunction "2_2") (pintype "passive"))
      (node (ref "C41") (pin "2") (pinfunction "2_2") (pintype "passive"))
      (node (ref "C42") (pin "2") (pinfunction "2_2") (pintype "passive"))
      (node (ref "C5") (pin "2") (pinfunction "2_2") (pintype "passive"))
      (node (ref "C6") (pin "2") (pinfunction "2_2") (pintype "passive"))
      (node (ref "C8") (pin "2") (pinfunction "2_2") (pintype "passive"))
      (node (ref "C9") (pin "2") (pinfunction "2_2") (pintype "passive"))
      (node (ref "J1") (pin "C5") (pinfunction "GND_C5") (pintype "passive"))
      (node (ref "J2") (pin "2@1") (pinfunction "GND_2@1") (pintype "passive"))
      (node (ref "J2") (pin "2@2") (pinfunction "GND_2@2") (pintype "passive"))
      (node (ref "JP1") (pin "2") (pinfunction "2_2") (pintype "passive"))
      (node (ref "JP2") (pin "15") (pinfunction "15_15") (pintype "passive"))
      (node (ref "JP4") (pin "GND") (pinfunction "1_GND") (pintype "passive"))
      (node (ref "R17") (pin "2") (pinfunction "2_2") (pintype "passive"))
      (node (ref "R19") (pin "2") (pinfunction "2_2") (pintype "passive"))
      (node (ref "R2") (pin "2") (pinfunction "2_2") (pintype "passive"))
      (node (ref "R21") (pin "2") (pinfunction "2_2") (pintype "passive"))
      (node (ref "R24") (pin "2") (pinfunction "2_2") (pintype "passive"))
      (node (ref "R25") (pin "2") (pinfunction "2_2") (pintype "passive"))
      (node (ref "R28") (pin "2") (pinfunction "2_2") (pintype "passive"))
      (node (ref "R31") (pin "2") (pinfunction "2_2") (pintype "passive"))
      (node (ref "RESET") (pin "3") (pinfunction "3_3") (pintype "passive"))
      (node (ref "RESET") (pin "4") (pinfunction "4_4") (pintype "passive"))
      (node (ref "SETUP") (pin "1") (pinfunction "1_1") (pintype "passive"))
      (node (ref "SETUP") (pin "2") (pinfunction "2_2") (pintype "passive"))
      (node (ref "U$1") (pin "17") (pinfunction "PGND_17") (pintype "passive"))
      (node (ref "U$1") (pin "18") (pinfunction "PGND_18") (pintype "passive"))
      (node (ref "U$1") (pin "PAD") (pinfunction "PAD_PAD") (pintype "power_in"))
      (node (ref "U$1") (pin "PAD@1") (pinfunction "PAD_PAD@1") (pintype "power_in"))
      (node (ref "U$1") (pin "PAD@2") (pinfunction "PAD_PAD@2") (pintype "power_in"))
      (node (ref "U$1") (pin "PAD@3") (pinfunction "PAD_PAD@3") (pintype "power_in"))
      (node (ref "U$1") (pin "PAD@4") (pinfunction "PAD_PAD@4") (pintype "power_in"))
      (node (ref "U$1") (pin "PAD@5") (pinfunction "PAD_PAD@5") (pintype "power_in"))
      (node (ref "U$1") (pin "PAD@6") (pinfunction "PAD_PAD@6") (pintype "power_in"))
      (node (ref "U$1") (pin "PAD@7") (pinfunction "PAD_PAD@7") (pintype "power_in"))
      (node (ref "U$1") (pin "PAD@8") (pinfunction "PAD_PAD@8") (pintype "power_in"))
      (node (ref "U$1") (pin "PAD@9") (pinfunction "PAD_PAD@9") (pintype "power_in"))
      (node (ref "U$5") (pin "P$2") (pinfunction "P$2_P$2") (pintype "bidirectional"))
      (node (ref "U$5") (pin "P$6") (pinfunction "P$6_P$6") (pintype "bidirectional"))
      (node (ref "U$5") (pin "TP") (pinfunction "P$6_TP") (pintype "bidirectional"))
      (node (ref "U1") (pin "1") (pinfunction "GND_1") (pintype "bidirectional"))
      (node (ref "U1") (pin "14") (pinfunction "GND_14") (pintype "bidirectional"))
      (node (ref "U1") (pin "20") (pinfunction "GND_20") (pintype "bidirectional"))
      (node (ref "U1") (pin "21") (pinfunction "GND_21") (pintype "bidirectional"))
      (node (ref "U1") (pin "22") (pinfunction "GND_22") (pintype "bidirectional"))
      (node (ref "U1") (pin "3") (pinfunction "GND_3") (pintype "bidirectional"))
      (node (ref "U1") (pin "30") (pinfunction "GND_30") (pintype "bidirectional"))
      (node (ref "U1") (pin "32") (pinfunction "GND65...96_32") (pintype "bidirectional"))
      (node (ref "U1") (pin "33") (pinfunction "RSVD_33") (pintype "bidirectional"))
      (node (ref "U1") (pin "43") (pinfunction "GND_43") (pintype "bidirectional"))
      (node (ref "U1") (pin "5") (pinfunction "GND_5") (pintype "bidirectional"))
      (node (ref "U1") (pin "50") (pinfunction "GND_50") (pintype "bidirectional"))
      (node (ref "U1") (pin "54") (pinfunction "GND_54") (pintype "bidirectional"))
      (node (ref "U1") (pin "55") (pinfunction "GND_55") (pintype "bidirectional"))
      (node (ref "U1") (pin "57") (pinfunction "GND_57") (pintype "bidirectional"))
      (node (ref "U1") (pin "58") (pinfunction "GND_58") (pintype "bidirectional"))
      (node (ref "U1") (pin "59") (pinfunction "GND_59") (pintype "bidirectional"))
      (node (ref "U1") (pin "60") (pinfunction "GND_60") (pintype "bidirectional"))
      (node (ref "U1") (pin "61") (pinfunction "GND_61") (pintype "bidirectional"))
      (node (ref "U1") (pin "63") (pinfunction "GND_63") (pintype "bidirectional"))
      (node (ref "U1") (pin "64") (pinfunction "GND_64") (pintype "bidirectional"))
      (node (ref "U1") (pin "65") (pinfunction "GND65...96_65") (pintype "bidirectional"))
      (node (ref "U1") (pin "66") (pinfunction "GND65...96_66") (pintype "bidirectional"))
      (node (ref "U1") (pin "67") (pinfunction "GND65...96_67") (pintype "bidirectional"))
      (node (ref "U1") (pin "68") (pinfunction "GND65...96_68") (pintype "bidirectional"))
      (node (ref "U1") (pin "69") (pinfunction "GND65...96_69") (pintype "bidirectional"))
      (node (ref "U1") (pin "70") (pinfunction "GND65...96_70") (pintype "bidirectional"))
      (node (ref "U1") (pin "71") (pinfunction "GND65...96_71") (pintype "bidirectional"))
      (node (ref "U1") (pin "72") (pinfunction "GND65...96_72") (pintype "bidirectional"))
      (node (ref "U1") (pin "73") (pinfunction "GND65...96_73") (pintype "bidirectional"))
      (node (ref "U1") (pin "74") (pinfunction "GND65...96_74") (pintype "bidirectional"))
      (node (ref "U1") (pin "75") (pinfunction "GND65...96_75") (pintype "bidirectional"))
      (node (ref "U1") (pin "76") (pinfunction "GND65...96_76") (pintype "bidirectional"))
      (node (ref "U1") (pin "77") (pinfunction "GND65...96_77") (pintype "bidirectional"))
      (node (ref "U1") (pin "78") (pinfunction "GND65...96_78") (pintype "bidirectional"))
      (node (ref "U1") (pin "79") (pinfunction "GND65...96_79") (pintype "bidirectional"))
      (node (ref "U1") (pin "80") (pinfunction "GND65...96_80") (pintype "bidirectional"))
      (node (ref "U1") (pin "81") (pinfunction "GND65...96_81") (pintype "bidirectional"))
      (node (ref "U1") (pin "82") (pinfunction "GND65...96_82") (pintype "bidirectional"))
      (node (ref "U1") (pin "83") (pinfunction "GND65...96_83") (pintype "bidirectional"))
      (node (ref "U1") (pin "84") (pinfunction "GND65...96_84") (pintype "bidirectional"))
      (node (ref "U1") (pin "85") (pinfunction "GND65...96_85") (pintype "bidirectional"))
      (node (ref "U1") (pin "86") (pinfunction "GND65...96_86") (pintype "bidirectional"))
      (node (ref "U1") (pin "87") (pinfunction "GND65...96_87") (pintype "bidirectional"))
      (node (ref "U1") (pin "88") (pinfunction "GND65...96_88") (pintype "bidirectional"))
      (node (ref "U1") (pin "89") (pinfunction "GND65...96_89") (pintype "bidirectional"))
      (node (ref "U1") (pin "90") (pinfunction "GND65...96_90") (pintype "bidirectional"))
      (node (ref "U1") (pin "91") (pinfunction "GND65...96_91") (pintype "bidirectional"))
      (node (ref "U1") (pin "92") (pinfunction "GND65...96_92") (pintype "bidirectional"))
      (node (ref "U1") (pin "93") (pinfunction "GND65...96_93") (pintype "bidirectional"))
      (node (ref "U1") (pin "94") (pinfunction "GND65...96_94") (pintype "bidirectional"))
      (node (ref "U1") (pin "95") (pinfunction "GND65...96_95") (pintype "bidirectional"))
      (node (ref "U1") (pin "96") (pinfunction "GND65...96_96") (pintype "bidirectional"))
      (node (ref "U2") (pin "1") (pinfunction "1/OE_1") (pintype "bidirectional"))
      (node (ref "U2") (pin "10") (pinfunction "GND_10") (pintype "bidirectional"))
      (node (ref "U2") (pin "11") (pinfunction "GND_11") (pintype "bidirectional"))
      (node (ref "U2") (pin "16") (pinfunction "2/OE_16") (pintype "bidirectional"))
      (node (ref "U2") (pin "9") (pinfunction "2A2_9") (pintype "bidirectional"))
      (node (ref "U3") (pin "12") (pinfunction "VSSA_12") (pintype "power_in"))
      (node (ref "U3") (pin "18") (pinfunction "VSS_4_18") (pintype "power_in"))
      (node (ref "U3") (pin "60") (pinfunction "BOOT0_60") (pintype "bidirectional"))
      (node (ref "U3") (pin "63") (pinfunction "VSS_3_63") (pintype "power_in"))
      (node (ref "U4") (pin "1") (pinfunction "CTG_1") (pintype "bidirectional"))
      (node (ref "U4") (pin "4") (pinfunction "GND_4") (pintype "bidirectional"))
      (node (ref "U4") (pin "6") (pinfunction "QST_6") (pintype "bidirectional"))
      (node (ref "U4") (pin "EP") (pinfunction "GND_EP") (pintype "bidirectional"))
      (node (ref "U5") (pin "3") (pinfunction "GND_3") (pintype "bidirectional"))
      (node (ref "U6") (pin "3") (pinfunction "GND_3") (pintype "bidirectional"))
      (node (ref "U8") (pin "1") (pinfunction "1/OE_1") (pintype "bidirectional"))
      (node (ref "U8") (pin "10") (pinfunction "GND_10") (pintype "bidirectional"))
      (node (ref "U8") (pin "11") (pinfunction "GND_11") (pintype "bidirectional"))
      (node (ref "U8") (pin "12") (pinfunction "2B2_12") (pintype "bidirectional"))
      (node (ref "U8") (pin "16") (pinfunction "2/OE_16") (pintype "bidirectional"))
      (node (ref "U8") (pin "4") (pinfunction "1DIR_4") (pintype "bidirectional"))
      (node (ref "U8") (pin "5") (pinfunction "2DIR_5") (pintype "bidirectional"))
      (node (ref "U9") (pin "2") (pinfunction "GND_2") (pintype "passive"))
      (node (ref "X1") (pin "GND") (pinfunction "GND_GND") (pintype "bidirectional"))
      (node (ref "X1") (pin "MT1") (pinfunction "GND_MT1") (pintype "bidirectional"))
      (node (ref "X1") (pin "MT2") (pinfunction "GND_MT2") (pintype "bidirectional"))
    )
    (net (code "39") (name "ILIM") (class "Default")
      (node (ref "R2") (pin "1") (pinfunction "1_1") (pintype "passive"))
      (node (ref "U$1") (pin "10") (pinfunction "ILIM_10") (pintype "output"))
    )
    (net (code "40") (name "LED1") (class "Default")
      (node (ref "BLUE_LED_0603") (pin "A") (pinfunction "A_A") (pintype "passive"))
      (node (ref "R10") (pin "1") (pinfunction "1_1") (pintype "passive"))
    )
    (net (code "41") (name "Net-(LED2-2)") (class "Default")
      (node (ref "LED2") (pin "BLUE") (pinfunction "2_BLUE") (pintype "passive"))
      (node (ref "R11") (pin "1") (pinfunction "1_1") (pintype "passive"))
    )
    (net (code "42") (name "Net-(LED2-3)") (class "Default")
      (node (ref "LED2") (pin "GREEN") (pinfunction "3_GREEN") (pintype "passive"))
      (node (ref "R9") (pin "1") (pinfunction "1_1") (pintype "passive"))
    )
    (net (code "43") (name "Net-(LED2-4)") (class "Default")
      (node (ref "LED2") (pin "RED") (pinfunction "4_RED") (pintype "passive"))
      (node (ref "R12") (pin "1") (pinfunction "1_1") (pintype "passive"))
    )
    (net (code "44") (name "Net-(R4-Pad2)") (class "Default")
      (node (ref "R4") (pin "2") (pinfunction "2_2") (pintype "passive"))
      (node (ref "RED_LED_0603") (pin "C") (pinfunction "C_C") (pintype "passive"))
    )
    (net (code "45") (name "Net-(U$1-OTG)") (class "Default")
      (node (ref "R16") (pin "1") (pinfunction "1_1") (pintype "passive"))
      (node (ref "U$1") (pin "8") (pinfunction "OTG_8") (pintype "bidirectional"))
    )
    (net (code "46") (name "Net-(U$1-TS)") (class "Default")
      (node (ref "R18") (pin "2") (pinfunction "2_2") (pintype "passive"))
      (node (ref "R19") (pin "1") (pinfunction "1_1") (pintype "passive"))
      (node (ref "U$1") (pin "11") (pinfunction "TS_11") (pintype "bidirectional"))
      (node (ref "U$1") (pin "12") (pinfunction "~{QON}_12") (pintype "bidirectional"))
    )
    (net (code "47") (name "Net-(U3-VCAP_1)") (class "Default")
      (node (ref "C35") (pin "1") (pinfunction "1_1") (pintype "passive"))
      (node (ref "U3") (pin "31") (pinfunction "VCAP_1_31") (pintype "power_in"))
    )
    (net (code "48") (name "Net-(U3-VCAP_2)") (class "Default")
      (node (ref "C32") (pin "1") (pinfunction "1_1") (pintype "passive"))
      (node (ref "U3") (pin "47") (pinfunction "VCAP_2_47") (pintype "power_in"))
    )
    (net (code "49") (name "Net-(U4-CELL)") (class "Default")
      (node (ref "C39") (pin "1") (pinfunction "1_1") (pintype "passive"))
      (node (ref "R23") (pin "1") (pinfunction "1_1") (pintype "passive"))
      (node (ref "U4") (pin "2") (pinfunction "CELL_2") (pintype "bidirectional"))
    )
    (net (code "50") (name "Net-(U4-VDD)") (class "Default")
      (node (ref "C38") (pin "1") (pinfunction "1_1") (pintype "passive"))
      (node (ref "R22") (pin "1") (pinfunction "1_1") (pintype "passive"))
      (node (ref "U4") (pin "3") (pinfunction "VDD_3") (pintype "bidirectional"))
    )
    (net (code "51") (name "OSC32_IN_UC") (class "Default")
      (node (ref "C34") (pin "1") (pinfunction "1_1") (pintype "passive"))
      (node (ref "U3") (pin "3") (pinfunction "PC14_3") (pintype "bidirectional"))
      (node (ref "Y1") (pin "X1") (pinfunction "1_X1") (pintype "passive"))
    )
    (net (code "52") (name "OSC32_OUT_UC") (class "Default")
      (node (ref "C33") (pin "1") (pinfunction "1_1") (pintype "passive"))
      (node (ref "U3") (pin "4") (pinfunction "PC15_4") (pintype "bidirectional"))
      (node (ref "Y1") (pin "X2") (pinfunction "2_X2") (pintype "passive"))
    )
    (net (code "53") (name "OSC_IN_UC") (class "Default")
      (node (ref "C28") (pin "1") (pinfunction "1_1") (pintype "passive"))
      (node (ref "U3") (pin "5") (pinfunction "PH0/OSC_IN_5") (pintype "bidirectional"))
      (node (ref "Y2") (pin "1") (pinfunction "1_1") (pintype "passive"))
    )
    (net (code "54") (name "OSC_OUT_UC") (class "Default")
      (node (ref "C26") (pin "1") (pinfunction "1_1") (pintype "passive"))
      (node (ref "U3") (pin "6") (pinfunction "PH1/OSC_OUT_6") (pintype "bidirectional"))
      (node (ref "Y2") (pin "3") (pinfunction "2_3") (pintype "passive"))
    )
    (net (code "55") (name "PA8_PM_SCL") (class "Default")
      (node (ref "R14") (pin "1") (pinfunction "1_1") (pintype "passive"))
      (node (ref "U$1") (pin "5") (pinfunction "SCL_5") (pintype "output"))
      (node (ref "U$9") (pin "P$1") (pinfunction "TP_P$1") (pintype "bidirectional"))
      (node (ref "U3") (pin "41") (pinfunction "PA8_41") (pintype "bidirectional"))
      (node (ref "U4") (pin "7") (pinfunction "SCL_7") (pintype "bidirectional"))
    )
    (net (code "56") (name "PC9_PM_SDA") (class "Default")
      (node (ref "R13") (pin "1") (pinfunction "1_1") (pintype "passive"))
      (node (ref "U$1") (pin "6") (pinfunction "SDA_6") (pintype "bidirectional"))
      (node (ref "U$8") (pin "P$1") (pinfunction "TP_P$1") (pintype "bidirectional"))
      (node (ref "U3") (pin "40") (pinfunction "PC9_40") (pintype "bidirectional"))
      (node (ref "U4") (pin "8") (pinfunction "SDA_8") (pintype "bidirectional"))
    )
    (net (code "57") (name "PMID") (class "Default")
      (node (ref "C5") (pin "1") (pinfunction "1_1") (pintype "passive"))
      (node (ref "U$1") (pin "23") (pinfunction "PMID_23") (pintype "passive"))
    )
    (net (code "58") (name "PWR_UB") (class "Default")
      (node (ref "R1") (pin "1") (pinfunction "1_1") (pintype "passive"))
      (node (ref "U1") (pin "15") (pinfunction "PWR_ON_15") (pintype "bidirectional"))
      (node (ref "U5") (pin "4") (pinfunction "B_4") (pintype "bidirectional"))
    )
    (net (code "59") (name "PWR_UC") (class "Default")
      (node (ref "R29") (pin "1") (pinfunction "1_1") (pintype "passive"))
      (node (ref "U3") (pin "28") (pinfunction "PB2_28") (pintype "bidirectional"))
      (node (ref "U5") (pin "2") (pinfunction "A_2") (pintype "bidirectional"))
    )
    (net (code "60") (name "P_3V3") (class "Default")
      (node (ref "C18") (pin "1") (pinfunction "1_1") (pintype "passive"))
      (node (ref "C19") (pin "1") (pinfunction "1_1") (pintype "passive"))
      (node (ref "U2") (pin "3") (pinfunction "VCCA_3") (pintype "bidirectional"))
      (node (ref "U2") (pin "4") (pinfunction "1DIR_4") (pintype "bidirectional"))
      (node (ref "U2") (pin "5") (pinfunction "2DIR_5") (pintype "bidirectional"))
      (node (ref "U8") (pin "3") (pinfunction "VCCA_3") (pintype "bidirectional"))
      (node (ref "U9") (pin "1") (pinfunction "VOUT_1") (pintype "output"))
    )
    (net (code "61") (name "REGN") (class "Default")
      (node (ref "C25") (pin "1") (pinfunction "1_1") (pintype "passive"))
      (node (ref "R18") (pin "1") (pinfunction "1_1") (pintype "passive"))
      (node (ref "U$1") (pin "22") (pinfunction "REGN_22") (pintype "bidirectional"))
    )
    (net (code "62") (name "RESET_UB") (class "Default")
      (node (ref "U1") (pin "18") (pinfunction "RESET_N_18") (pintype "bidirectional"))
      (node (ref "U6") (pin "4") (pinfunction "B_4") (pintype "bidirectional"))
    )
    (net (code "63") (name "RESET_UC") (class "Default")
      (node (ref "R30") (pin "1") (pinfunction "1_1") (pintype "passive"))
      (node (ref "U3") (pin "24") (pinfunction "PC4_24") (pintype "bidirectional"))
      (node (ref "U6") (pin "2") (pinfunction "A_2") (pintype "bidirectional"))
    )
    (net (code "64") (name "RGB_BLUE") (class "Default")
      (node (ref "R11") (pin "2") (pinfunction "2_2") (pintype "passive"))
      (node (ref "U$13") (pin "P$1") (pinfunction "TP_P$1") (pintype "bidirectional"))
      (node (ref "U3") (pin "17") (pinfunction "PA3_17") (pintype "bidirectional"))
    )
    (net (code "65") (name "RGB_GREEN") (class "Default")
      (node (ref "R9") (pin "2") (pinfunction "2_2") (pintype "passive"))
      (node (ref "U$12") (pin "P$1") (pinfunction "TP_P$1") (pintype "bidirectional"))
      (node (ref "U3") (pin "16") (pinfunction "PA2_16") (pintype "bidirectional"))
    )
    (net (code "66") (name "RGB_RED") (class "Default")
      (node (ref "R12") (pin "2") (pinfunction "2_2") (pintype "passive"))
      (node (ref "U$11") (pin "P$1") (pinfunction "TP_P$1") (pintype "bidirectional"))
      (node (ref "U3") (pin "15") (pinfunction "PA1_15") (pintype "bidirectional"))
    )
    (net (code "67") (name "RI_UB") (class "Default")
      (node (ref "R28") (pin "1") (pinfunction "1_1") (pintype "passive"))
      (node (ref "U1") (pin "7") (pinfunction "RI_7") (pintype "bidirectional"))
      (node (ref "U8") (pin "14") (pinfunction "1B2_14") (pintype "bidirectional"))
    )
    (net (code "68") (name "RI_UC") (class "Default")
      (node (ref "U3") (pin "33") (pinfunction "PB12_33") (pintype "bidirectional"))
      (node (ref "U8") (pin "7") (pinfunction "1A2_7") (pintype "bidirectional"))
    )
    (net (code "69") (name "RTS_UB") (class "Default")
      (node (ref "U1") (pin "10") (pinfunction "RTS_10") (pintype "bidirectional"))
      (node (ref "U2") (pin "15") (pinfunction "1B1_15") (pintype "bidirectional"))
    )
    (net (code "70") (name "RTS_UC") (class "Default")
      (node (ref "R24") (pin "1") (pinfunction "1_1") (pintype "passive"))
      (node (ref "U2") (pin "6") (pinfunction "1A1_6") (pintype "bidirectional"))
      (node (ref "U3") (pin "35") (pinfunction "PB14_35") (pintype "bidirectional"))
    )
    (net (code "71") (name "RX") (class "Default")
      (node (ref "JP1") (pin "4") (pinfunction "4_4") (pintype "passive"))
      (node (ref "U3") (pin "43") (pinfunction "PA10_43") (pintype "bidirectional"))
    )
    (net (code "72") (name "RXD_UB") (class "Default")
      (node (ref "R21") (pin "1") (pinfunction "1_1") (pintype "passive"))
      (node (ref "U1") (pin "13") (pinfunction "RXD_13") (pintype "bidirectional"))
      (node (ref "U8") (pin "13") (pinfunction "2B1_13") (pintype "bidirectional"))
    )
    (net (code "73") (name "RXD_UC") (class "Default")
      (node (ref "U3") (pin "30") (pinfunction "PB11_30") (pintype "bidirectional"))
      (node (ref "U8") (pin "8") (pinfunction "2A1_8") (pintype "bidirectional"))
    )
    (net (code "74") (name "SIM_CLK") (class "Default")
      (node (ref "C12") (pin "1") (pinfunction "1_1") (pintype "passive"))
      (node (ref "J1") (pin "C3") (pinfunction "CLK_C3") (pintype "passive"))
      (node (ref "U1") (pin "38") (pinfunction "SIM_CLK_38") (pintype "bidirectional"))
    )
    (net (code "75") (name "SIM_DET") (class "Default")
      (node (ref "U1") (pin "42") (pinfunction "SIM_DET_42") (pintype "bidirectional"))
    )
    (net (code "76") (name "SIM_IO") (class "Default")
      (node (ref "C13") (pin "1") (pinfunction "1_1") (pintype "passive"))
      (node (ref "J1") (pin "C7") (pinfunction "I/O_C7") (pintype "passive"))
      (node (ref "U1") (pin "39") (pinfunction "SIM_IO_39") (pintype "bidirectional"))
    )
    (net (code "77") (name "SIM_RST") (class "Default")
      (node (ref "C10") (pin "1") (pinfunction "1_1") (pintype "passive"))
      (node (ref "J1") (pin "C2") (pinfunction "RST_C2") (pintype "passive"))
      (node (ref "U1") (pin "40") (pinfunction "SIM_RST_40") (pintype "bidirectional"))
    )
    (net (code "78") (name "SIM_VCC") (class "Default")
      (node (ref "C11") (pin "1") (pinfunction "1_1") (pintype "passive"))
      (node (ref "C14") (pin "1") (pinfunction "1_1") (pintype "passive"))
      (node (ref "J1") (pin "C1") (pinfunction "VCC_C1") (pintype "passive"))
      (node (ref "J1") (pin "C6") (pinfunction "VPP_C6") (pintype "passive"))
      (node (ref "U1") (pin "41") (pinfunction "VSIM_41") (pintype "bidirectional"))
    )
    (net (code "79") (name "STAT") (class "Default")
      (node (ref "R4") (pin "1") (pinfunction "1_1") (pintype "passive"))
      (node (ref "U$1") (pin "4") (pinfunction "STAT_4") (pintype "bidirectional"))
    )
    (net (code "80") (name "SW1") (class "Default")
      (node (ref "C7") (pin "2") (pinfunction "2_2") (pintype "passive"))
      (node (ref "U$1") (pin "19") (pinfunction "SW_19") (pintype "power_in"))
      (node (ref "U$1") (pin "20") (pinfunction "SW_20") (pintype "power_in"))
      (node (ref "U$4") (pin "P$1") (pinfunction "1_P$1") (pintype "passive"))
    )
    (net (code "81") (name "SW2") (class "Default")
      (node (ref "U$5") (pin "P$1") (pinfunction "P$1_P$1") (pintype "bidirectional"))
      (node (ref "U$6") (pin "1") (pinfunction "1_1") (pintype "passive"))
    )
    (net (code "82") (name "TX") (class "Default")
      (node (ref "JP1") (pin "3") (pinfunction "3_3") (pintype "passive"))
      (node (ref "U3") (pin "42") (pinfunction "PA9_42") (pintype "bidirectional"))
    )
    (net (code "83") (name "TXD_UB") (class "Default")
      (node (ref "U1") (pin "12") (pinfunction "TXD_12") (pintype "bidirectional"))
      (node (ref "U2") (pin "14") (pinfunction "1B2_14") (pintype "bidirectional"))
    )
    (net (code "84") (name "TXD_UC") (class "Default")
      (node (ref "R25") (pin "1") (pinfunction "1_1") (pintype "passive"))
      (node (ref "U2") (pin "7") (pinfunction "1A2_7") (pintype "bidirectional"))
      (node (ref "U3") (pin "29") (pinfunction "PB10_29") (pintype "bidirectional"))
    )
    (net (code "85") (name "USB_DM") (class "Default")
      (node (ref "R6") (pin "2") (pinfunction "2_2") (pintype "passive"))
      (node (ref "U$1") (pin "3") (pinfunction "~{PG}_3") (pintype "output"))
      (node (ref "U$7") (pin "P$2") (pinfunction "P$2_P$2") (pintype "bidirectional"))
      (node (ref "X1") (pin "D-") (pinfunction "D-_D-") (pintype "bidirectional"))
    )
    (net (code "86") (name "USB_DM_UC") (class "Default")
      (node (ref "R6") (pin "1") (pinfunction "1_1") (pintype "passive"))
      (node (ref "U3") (pin "44") (pinfunction "PA11_44") (pintype "bidirectional"))
    )
    (net (code "87") (name "USB_DP") (class "Default")
      (node (ref "R5") (pin "2") (pinfunction "2_2") (pintype "passive"))
      (node (ref "U$1") (pin "2") (pinfunction "PSEL_2") (pintype "output"))
      (node (ref "U$7") (pin "P$1") (pinfunction "P$1_P$1") (pintype "bidirectional"))
      (node (ref "X1") (pin "D+") (pinfunction "D+_D+") (pintype "bidirectional"))
    )
    (net (code "88") (name "USB_DP_UC") (class "Default")
      (node (ref "R5") (pin "1") (pinfunction "1_1") (pintype "passive"))
      (node (ref "U3") (pin "45") (pinfunction "PA12_45") (pintype "bidirectional"))
    )
    (net (code "89") (name "VBAT") (class "Default")
      (node (ref "JP2") (pin "16") (pinfunction "16_16") (pintype "passive"))
      (node (ref "R7") (pin "1") (pinfunction "1_1") (pintype "passive"))
      (node (ref "U3") (pin "1") (pinfunction "VBAT_1") (pintype "power_in"))
    )
    (net (code "90") (name "VBUS") (class "Default")
      (node (ref "JP3") (pin "1") (pinfunction "1_1") (pintype "passive"))
      (node (ref "U$3") (pin "ANODE") (pinfunction "ANODE_ANODE") (pintype "bidirectional"))
      (node (ref "X1") (pin "VBUS") (pinfunction "VBUS_VBUS") (pintype "bidirectional"))
    )
    (net (code "91") (name "VIN") (class "Default")
      (node (ref "C4") (pin "1") (pinfunction "1_1") (pintype "passive"))
      (node (ref "JP1") (pin "1") (pinfunction "1_1") (pintype "passive"))
      (node (ref "U$1") (pin "1") (pinfunction "VBUS_1") (pintype "power_in"))
      (node (ref "U$1") (pin "24") (pinfunction "VBUS_24") (pintype "passive"))
      (node (ref "U$3") (pin "CATHODE") (pinfunction "CATHODE_CATHODE") (pintype "bidirectional"))
    )
    (net (code "92") (name "V_BCKP") (class "Default")
      (node (ref "R1") (pin "2") (pinfunction "2_2") (pintype "passive"))
      (node (ref "U1") (pin "2") (pinfunction "V_BCKP_2") (pintype "bidirectional"))
    )
    (net (code "93") (name "V_INT") (class "Default")
      (node (ref "C21") (pin "1") (pinfunction "1_1") (pintype "passive"))
      (node (ref "C22") (pin "1") (pinfunction "1_1") (pintype "passive"))
      (node (ref "R3") (pin "2") (pinfunction "2_2") (pintype "passive"))
      (node (ref "U1") (pin "4") (pinfunction "V_INT_4") (pintype "bidirectional"))
      (node (ref "U2") (pin "2") (pinfunction "VCCB_2") (pintype "bidirectional"))
      (node (ref "U8") (pin "2") (pinfunction "VCCB_2") (pintype "bidirectional"))
    )
    (net (code "94") (name "WKP") (class "Default")
      (node (ref "JP1") (pin "5") (pinfunction "5_5") (pintype "passive"))
      (node (ref "U3") (pin "14") (pinfunction "WKUP/PA0_14") (pintype "bidirectional"))
    )
    (net (code "95") (name "unconnected-(RESET-Pad1)") (class "Default")
      (node (ref "RESET") (pin "1") (pinfunction "1_1") (pintype "passive"))
    )
    (net (code "96") (name "unconnected-(SETUP-Pad4)") (class "Default")
      (node (ref "SETUP") (pin "4") (pinfunction "4_4") (pintype "passive"))
    )
    (net (code "97") (name "unconnected-(U1-DCD-Pad8)") (class "Default")
      (node (ref "U1") (pin "8") (pinfunction "DCD_8") (pintype "bidirectional"))
    )
    (net (code "98") (name "unconnected-(U1-DSR-Pad6)") (class "Default")
      (node (ref "U1") (pin "6") (pinfunction "DSR_6") (pintype "bidirectional"))
    )
    (net (code "99") (name "unconnected-(U1-GPIO1-Pad16)") (class "Default")
      (node (ref "U1") (pin "16") (pinfunction "GPIO1_16") (pintype "bidirectional"))
    )
    (net (code "100") (name "unconnected-(U1-GPIO2-Pad23)") (class "Default")
      (node (ref "U1") (pin "23") (pinfunction "GPIO2_23") (pintype "bidirectional"))
    )
    (net (code "101") (name "unconnected-(U1-GPIO3-Pad24)") (class "Default")
      (node (ref "U1") (pin "24") (pinfunction "GPIO3_24") (pintype "bidirectional"))
    )
    (net (code "102") (name "unconnected-(U1-GPIO4-Pad25)") (class "Default")
      (node (ref "U1") (pin "25") (pinfunction "GPIO4_25") (pintype "bidirectional"))
    )
    (net (code "103") (name "unconnected-(U1-I2S_CLK-Pad36)") (class "Default")
      (node (ref "U1") (pin "36") (pinfunction "I2S_CLK_36") (pintype "bidirectional"))
    )
    (net (code "104") (name "unconnected-(U1-I2S_RXD-Pad37)") (class "Default")
      (node (ref "U1") (pin "37") (pinfunction "I2S_RXD_37") (pintype "bidirectional"))
    )
    (net (code "105") (name "unconnected-(U1-I2S_TXD-Pad35)") (class "Default")
      (node (ref "U1") (pin "35") (pinfunction "I2S_TXD_35") (pintype "bidirectional"))
    )
    (net (code "106") (name "unconnected-(U1-I2S_WA-Pad34)") (class "Default")
      (node (ref "U1") (pin "34") (pinfunction "I2S_WA_34") (pintype "bidirectional"))
    )
    (net (code "107") (name "unconnected-(U1-MIC_BIAS-Pad46)") (class "Default")
      (node (ref "U1") (pin "46") (pinfunction "MIC_BIAS_46") (pintype "bidirectional"))
    )
    (net (code "108") (name "unconnected-(U1-MIC_GND-Pad47)") (class "Default")
      (node (ref "U1") (pin "47") (pinfunction "MIC_GND_47") (pintype "bidirectional"))
    )
    (net (code "109") (name "unconnected-(U1-MIC_N-Pad48)") (class "Default")
      (node (ref "U1") (pin "48") (pinfunction "MIC_N_48") (pintype "bidirectional"))
    )
    (net (code "110") (name "unconnected-(U1-MIC_P-Pad49)") (class "Default")
      (node (ref "U1") (pin "49") (pinfunction "MIC_P_49") (pintype "bidirectional"))
    )
    (net (code "111") (name "unconnected-(U1-RSVD-Pad19)") (class "Default")
      (node (ref "U1") (pin "19") (pinfunction "RSVD_19") (pintype "bidirectional"))
    )
    (net (code "112") (name "unconnected-(U1-RSVD-Pad31)") (class "Default")
      (node (ref "U1") (pin "31") (pinfunction "RSVD_31") (pintype "bidirectional"))
    )
    (net (code "113") (name "unconnected-(U1-RXD_AUX{slash}USB_D--Pad28)") (class "Default")
      (node (ref "U1") (pin "28") (pinfunction "RXD_AUX/USB_D-_28") (pintype "bidirectional"))
    )
    (net (code "114") (name "unconnected-(U1-SCL-Pad27)") (class "Default")
      (node (ref "U1") (pin "27") (pinfunction "SCL_27") (pintype "bidirectional"))
    )
    (net (code "115") (name "unconnected-(U1-SDA-Pad26)") (class "Default")
      (node (ref "U1") (pin "26") (pinfunction "SDA_26") (pintype "bidirectional"))
    )
    (net (code "116") (name "unconnected-(U1-SPK_N-Pad45)") (class "Default")
      (node (ref "U1") (pin "45") (pinfunction "SPK_N_45") (pintype "bidirectional"))
    )
    (net (code "117") (name "unconnected-(U1-SPK_P-Pad44)") (class "Default")
      (node (ref "U1") (pin "44") (pinfunction "SPK_P_44") (pintype "bidirectional"))
    )
    (net (code "118") (name "unconnected-(U1-TXD_AUX{slash}USB_D+-Pad29)") (class "Default")
      (node (ref "U1") (pin "29") (pinfunction "TXD_AUX/USB_D+_29") (pintype "bidirectional"))
    )
    (net (code "119") (name "unconnected-(U1-VUSB_DET-Pad17)") (class "Default")
      (node (ref "U1") (pin "17") (pinfunction "VUSB_DET_17") (pintype "bidirectional"))
    )
    (net (code "120") (name "unconnected-(U2-2B2-Pad12)") (class "Default")
      (node (ref "U2") (pin "12") (pinfunction "2B2_12") (pintype "bidirectional"))
    )
    (net (code "121") (name "unconnected-(U8-2A2-Pad9)") (class "Default")
      (node (ref "U8") (pin "9") (pinfunction "2A2_9") (pintype "bidirectional"))
    )
    (net (code "122") (name "unconnected-(U9-OC-Pad3)") (class "Default")
      (node (ref "U9") (pin "3") (pinfunction "OC_3") (pintype "output"))
    )
    (net (code "123") (name "~{BATT_INT_PC13}") (class "Default")
      (node (ref "R15") (pin "1") (pinfunction "1_1") (pintype "passive"))
      (node (ref "U$1") (pin "7") (pinfunction "INT_7") (pintype "bidirectional"))
      (node (ref "U3") (pin "2") (pinfunction "PC13_2") (pintype "bidirectional"))
      (node (ref "U4") (pin "5") (pinfunction "ALT_5") (pintype "bidirectional"))
    )
    (net (code "124") (name "~{CE}") (class "Default")
      (node (ref "R17") (pin "1") (pinfunction "1_1") (pintype "passive"))
      (node (ref "U$1") (pin "9") (pinfunction "~{CE}_9") (pintype "output"))
    )
    (net (code "125") (name "~{RST}") (class "Default")
      (node (ref "C6") (pin "1") (pinfunction "1_1") (pintype "passive"))
      (node (ref "JP2") (pin "17") (pinfunction "17_17") (pintype "passive"))
      (node (ref "R8") (pin "1") (pinfunction "1_1") (pintype "passive"))
      (node (ref "RESET") (pin "2") (pinfunction "2_2") (pintype "passive"))
      (node (ref "U3") (pin "7") (pinfunction "NRST_7") (pintype "power_in"))
    )
    (net (code "126") (name "~{SETUP}") (class "Default")
      (node (ref "SETUP") (pin "3") (pinfunction "3_3") (pintype "passive"))
      (node (ref "U3") (pin "38") (pinfunction "PC7_38") (pintype "bidirectional"))
    )
  )
)
